# Sh1_MPU.net
KiCad netlist of a schematic drawn in Altium Designer
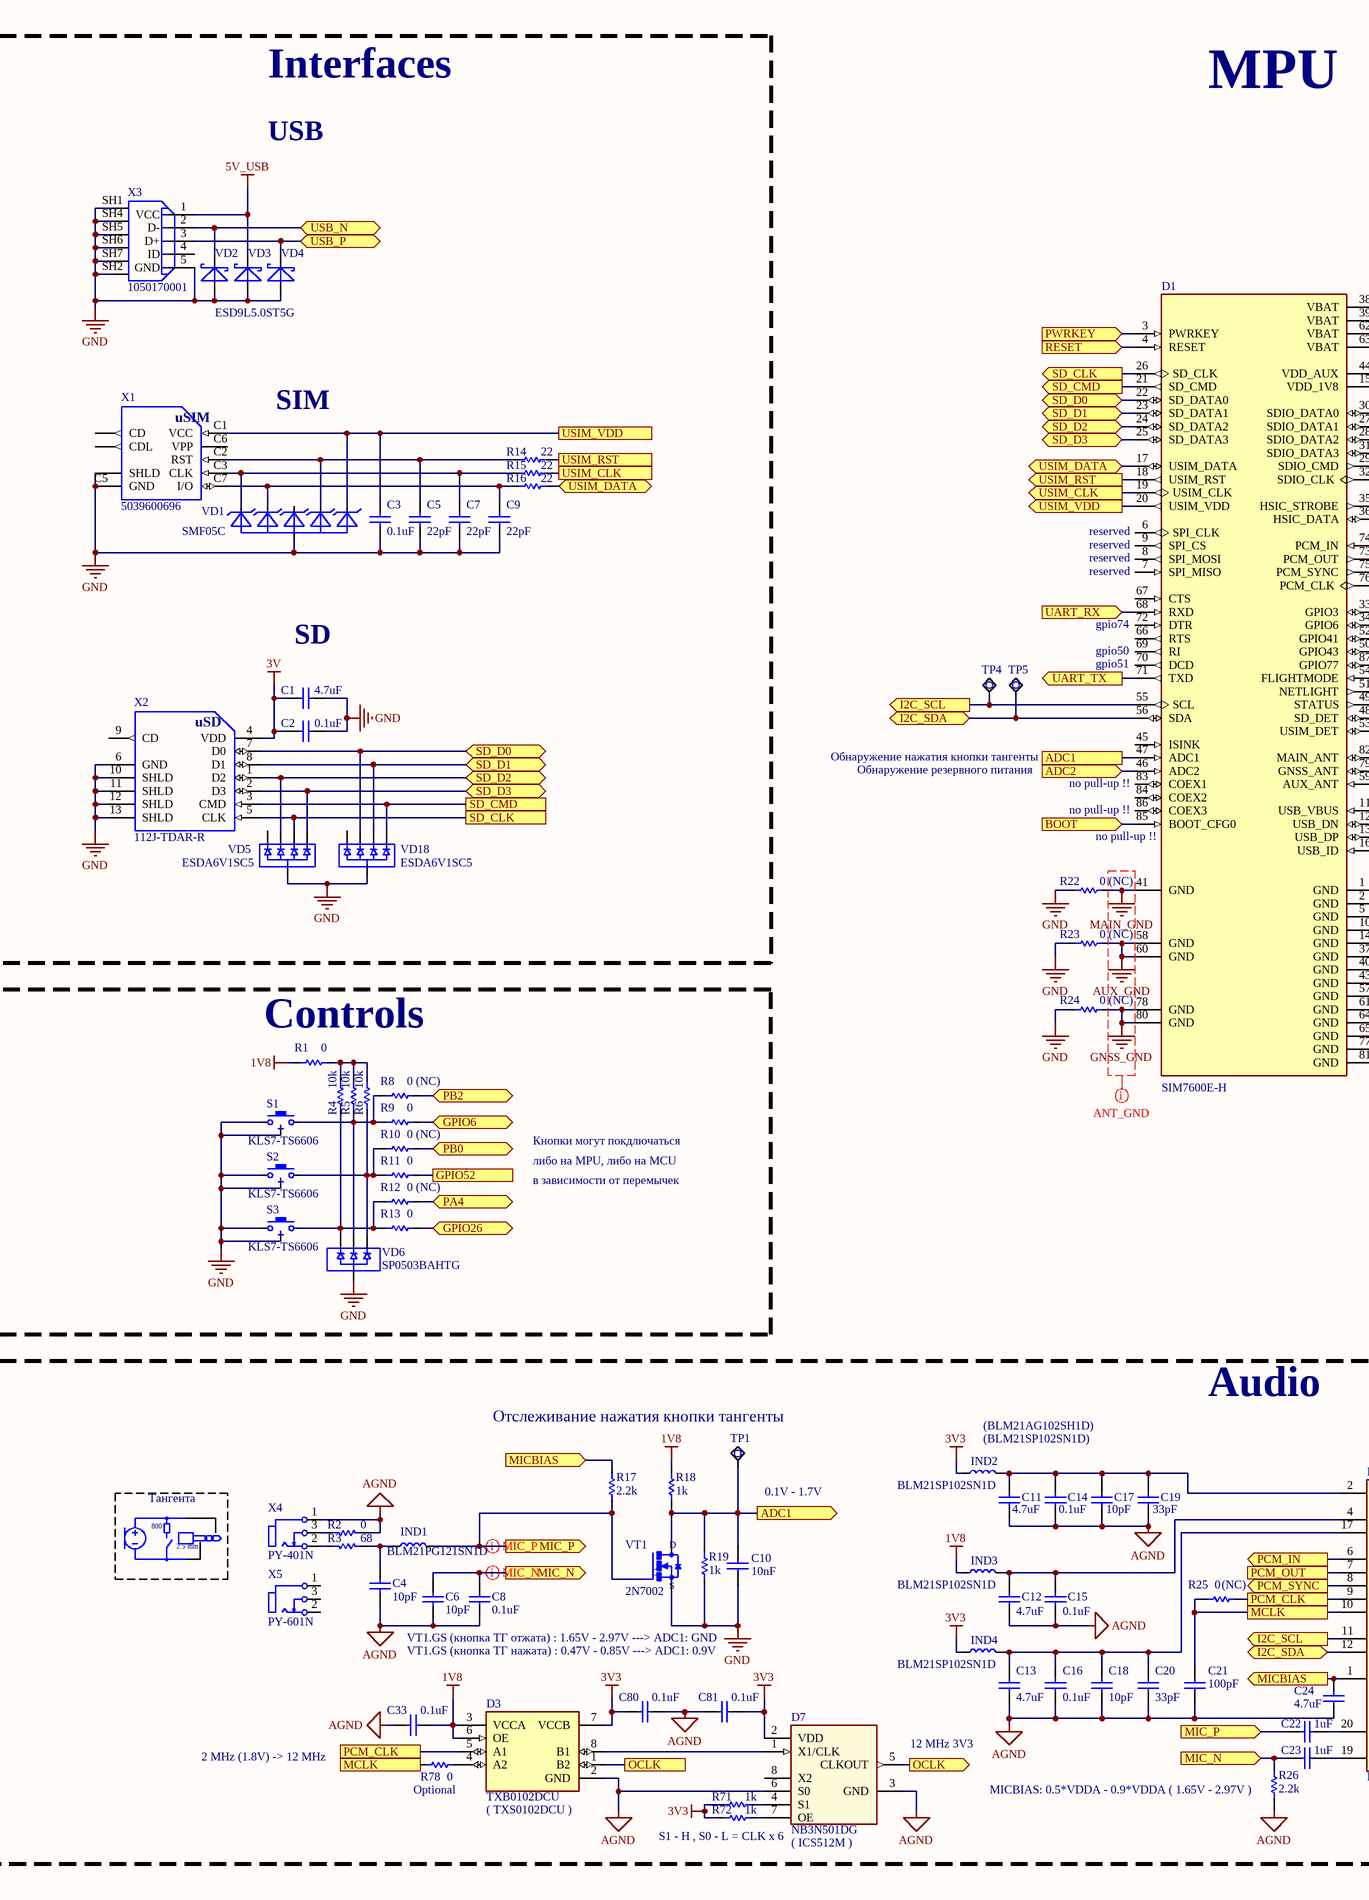
[diagram p0: Sh1_MPU.SchDoc, left]
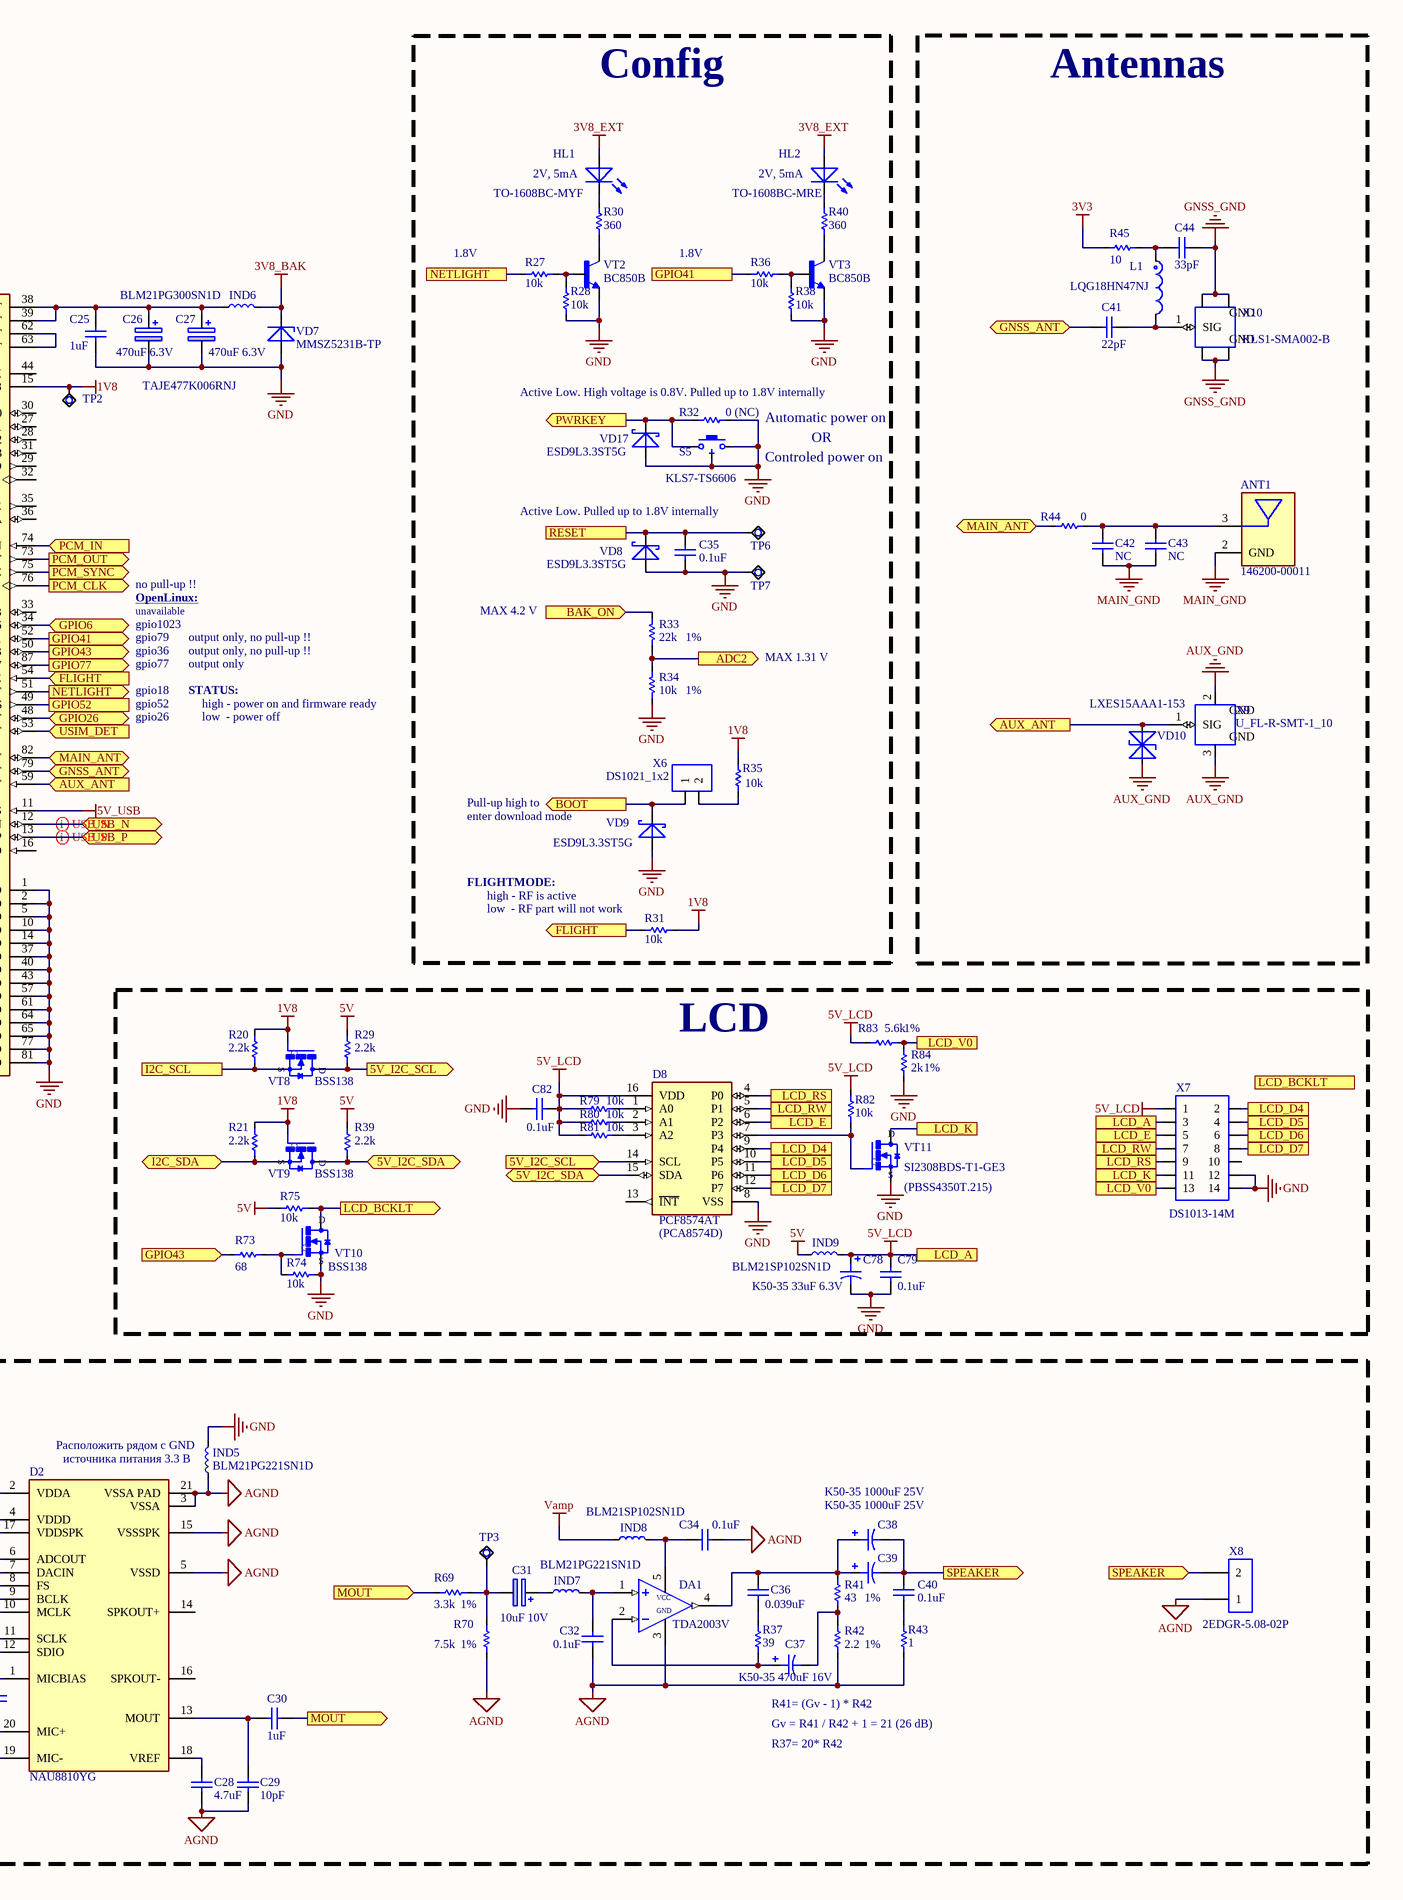
[diagram p1: Sh1_MPU.SchDoc, right]

(export (version "E")
  (design (tool "Eeschema 10.0.6"))
  (components
    (comp (ref "ANT1")
      (value "146200-00011")
      (footprint "Molex_146200-0011_MFG")
      (description "LTE Cellular Ceramic Antenna 698MHz-2.7GHz , SMT")
      (libsource (lib "MyCompLib") (part "146200-0001(11)"))
    )
    (comp (ref "C1")
      (value "4.7uF")
      (footprint "C_SMD0603")
      (description "GRM188R60J475KE19D")
      (libsource (lib "") (part "C_SMD_1"))
    )
    (comp (ref "C2")
      (value "0.1uF")
      (footprint "C_SMD0603")
      (description "GRM188R71H104KA93D")
      (libsource (lib "") (part "C_SMD_1"))
    )
    (comp (ref "C3")
      (value "0.1uF")
      (footprint "C_SMD0603")
      (description "GRM188R71H104KA93D")
      (libsource (lib "") (part "C_SMD_1"))
    )
    (comp (ref "C4")
      (value "10pF")
      (footprint "C_SMD0603")
      (description "GRM1885C1H100J")
      (libsource (lib "MyCompLib") (part "C_SMD"))
    )
    (comp (ref "C5")
      (value "22pF")
      (footprint "C_SMD0603")
      (description "GRM1885C1H220JA01D")
      (libsource (lib "") (part "C_SMD_1"))
    )
    (comp (ref "C6")
      (value "10pF")
      (footprint "C_SMD0603")
      (description "GRM1885C1H100J")
      (libsource (lib "MyCompLib") (part "C_SMD"))
    )
    (comp (ref "C7")
      (value "22pF")
      (footprint "C_SMD0603")
      (description "GRM1885C1H220JA01D")
      (libsource (lib "") (part "C_SMD_1"))
    )
    (comp (ref "C8")
      (value "0.1uF")
      (footprint "C_SMD0603")
      (description "GRM188R71H104KA93D")
      (libsource (lib "MyCompLib") (part "C_SMD"))
    )
    (comp (ref "C9")
      (value "22pF")
      (footprint "C_SMD0603")
      (description "GRM1885C1H220JA01D")
      (libsource (lib "") (part "C_SMD_1"))
    )
    (comp (ref "C10")
      (value "10nF")
      (footprint "C_SMD0603")
      (description "GRM188R71H103K")
      (libsource (lib "MyCompLib") (part "C_SMD"))
    )
    (comp (ref "C11")
      (value "4.7uF")
      (footprint "C_SMD0603")
      (description "GRM188R60J475KE19D")
      (libsource (lib "MyCompLib") (part "C_SMD"))
    )
    (comp (ref "C12")
      (value "4.7uF")
      (footprint "C_SMD0603")
      (description "GRM188R60J475KE19D")
      (libsource (lib "MyCompLib") (part "C_SMD"))
    )
    (comp (ref "C13")
      (value "4.7uF")
      (footprint "C_SMD0603")
      (description "GRM188R60J475KE19D")
      (libsource (lib "MyCompLib") (part "C_SMD"))
    )
    (comp (ref "C14")
      (value "0.1uF")
      (footprint "C_SMD0603")
      (description "GRM188R71H104KA93D")
      (libsource (lib "MyCompLib") (part "C_SMD"))
    )
    (comp (ref "C15")
      (value "0.1uF")
      (footprint "C_SMD0603")
      (description "GRM188R71H104KA93D")
      (libsource (lib "MyCompLib") (part "C_SMD"))
    )
    (comp (ref "C16")
      (value "0.1uF")
      (footprint "C_SMD0603")
      (description "GRM188R71H104KA93D")
      (libsource (lib "MyCompLib") (part "C_SMD"))
    )
    (comp (ref "C17")
      (value "10pF")
      (footprint "C_SMD0603")
      (description "GRM1885C1H100J")
      (libsource (lib "MyCompLib") (part "C_SMD"))
    )
    (comp (ref "C18")
      (value "10pF")
      (footprint "C_SMD0603")
      (description "GRM1885C1H100J")
      (libsource (lib "MyCompLib") (part "C_SMD"))
    )
    (comp (ref "C19")
      (value "33pF")
      (footprint "C_SMD0603")
      (description "GRM1885C1H330J")
      (libsource (lib "MyCompLib") (part "C_SMD"))
    )
    (comp (ref "C20")
      (value "33pF")
      (footprint "C_SMD0603")
      (description "GRM1885C1H330J")
      (libsource (lib "MyCompLib") (part "C_SMD"))
    )
    (comp (ref "C21")
      (value "100pF")
      (footprint "C_SMD0603")
      (description "GRM1885C1H101J")
      (libsource (lib "MyCompLib") (part "C_SMD"))
    )
    (comp (ref "C22")
      (value "1uF")
      (footprint "C_SMD0603")
      (description "GRM188R71E105KA12D")
      (libsource (lib "MyCompLib") (part "C_SMD"))
    )
    (comp (ref "C23")
      (value "1uF")
      (footprint "C_SMD0603")
      (description "GRM188R71E105KA12D")
      (libsource (lib "MyCompLib") (part "C_SMD"))
    )
    (comp (ref "C24")
      (value "4.7uF")
      (footprint "C_SMD0603")
      (description "GRM188R60J475KE19D")
      (libsource (lib "MyCompLib") (part "C_SMD"))
    )
    (comp (ref "C25")
      (value "1uF")
      (footprint "C_SMD0603")
      (description "GRM188R71E105KA12D")
      (libsource (lib "MyCompLib") (part "C_SMD"))
    )
    (comp (ref "C26")
      (value "470uF 6.3V")
      (footprint "TECAP_E")
      (description "293D477X06R3E2TE3\r\nКонденсатор танталовый SMD тип Е")
      (libsource (lib "MyCompLib") (part "C_SMD_Tantalum"))
    )
    (comp (ref "C27")
      (value "470uF 6.3V")
      (footprint "TECAP_E")
      (description "293D477X06R3E2TE3\r\nКонденсатор танталовый SMD тип Е")
      (libsource (lib "MyCompLib") (part "C_SMD_Tantalum"))
    )
    (comp (ref "C28")
      (value "4.7uF")
      (footprint "C_SMD0603")
      (description "GRM188R60J475KE19D")
      (libsource (lib "MyCompLib") (part "C_SMD"))
    )
    (comp (ref "C29")
      (value "10pF")
      (footprint "C_SMD0603")
      (description "GRM1885C1H100J")
      (libsource (lib "MyCompLib") (part "C_SMD"))
    )
    (comp (ref "C30")
      (value "1uF")
      (footprint "C_SMD1206")
      (description "GRM31MR71E105KA01L")
      (libsource (lib "MyCompLib") (part "C_SMD"))
    )
    (comp (ref "C31")
      (value "10uF 10V")
      (footprint "TECAP_B")
      (description "TAJB106K016RNJ\r\nКонденсатор танталовый SMD 10uF 10V тип B")
      (libsource (lib "") (part "C_SMD_Tantalum_1"))
    )
    (comp (ref "C32")
      (value "0.1uF")
      (footprint "C_SMD0603")
      (description "GRM188R71H104KA93D")
      (libsource (lib "MyCompLib") (part "C_SMD"))
    )
    (comp (ref "C33")
      (value "0.1uF")
      (footprint "C_SMD0402")
      (description "CL05B104KO5NNNC")
      (libsource (lib "MyCompLib") (part "C_SMD"))
    )
    (comp (ref "C34")
      (value "0.1uF")
      (footprint "C_SMD0603")
      (description "GRM188R71H104KA93D")
      (libsource (lib "MyCompLib") (part "C_SMD"))
    )
    (comp (ref "C35")
      (value "0.1uF")
      (footprint "C_SMD0603")
      (description "GRM188R71H104KA93D")
      (libsource (lib "MyCompLib") (part "C_SMD"))
    )
    (comp (ref "C36")
      (value "0.039uF")
      (footprint "C_SMD0603")
      (description "CC0603KRX7R9BB393")
      (libsource (lib "MyCompLib") (part "C_SMD"))
    )
    (comp (ref "C37")
      (value "K50-35 470uF 16V")
      (footprint "K50-35 8x11.5x3.5")
      (description "Конденсатор электролитический алюминиевый 470мкФ, 16В 8х12мм Р:3.5мм")
      (libsource (lib "MyCompLib") (part "K50-35"))
    )
    (comp (ref "C38")
      (value "K50-35 1000uF 25V")
      (footprint "K50-35 10x12.5x5")
      (description "Конденсатор электролитический алюминиевый 1000мкФ, 16В, 10x21мм")
      (libsource (lib "MyCompLib") (part "K50-35"))
    )
    (comp (ref "C39")
      (value "K50-35 1000uF 25V")
      (footprint "K50-35 10x12.5x5")
      (description "Конденсатор электролитический алюминиевый 1000мкФ, 16В, 10x21мм")
      (libsource (lib "MyCompLib") (part "K50-35"))
    )
    (comp (ref "C40")
      (value "0.1uF")
      (footprint "C_SMD0603")
      (description "GRM188R71H104KA93D")
      (libsource (lib "MyCompLib") (part "C_SMD"))
    )
    (comp (ref "C41")
      (value "22pF")
      (footprint "C_SMD0805")
      (description "GRM21A5C2E220J")
      (libsource (lib "MyCompLib") (part "C_SMD"))
    )
    (comp (ref "C42")
      (value "NС")
      (footprint "C_SMD0603")
      (description "0603 SMD Capacitor")
      (libsource (lib "MyCompLib") (part "C_SMD"))
    )
    (comp (ref "C43")
      (value "NС")
      (footprint "C_SMD0603")
      (description "0603 SMD Capacitor")
      (libsource (lib "MyCompLib") (part "C_SMD"))
    )
    (comp (ref "C44")
      (value "33pF")
      (footprint "C_SMD0603")
      (description "GRM1885C1H330J")
      (libsource (lib "MyCompLib") (part "C_SMD"))
    )
    (comp (ref "C78")
      (value "K50-35 33uF 6.3V")
      (footprint "K50-35mini 4x7x2")
      (description "Конденсатор электролитический алюминиевый 33 мкФ, 6.3 В, 4х7мм")
      (libsource (lib "MyCompLib") (part "K50-35"))
    )
    (comp (ref "C79")
      (value "0.1uF")
      (footprint "C_SMD0603")
      (description "GRM188R71H104KA93D")
      (libsource (lib "MyCompLib") (part "C_SMD"))
    )
    (comp (ref "C80")
      (value "0.1uF")
      (footprint "C_SMD0402")
      (description "CL05B104KO5NNNC")
      (libsource (lib "MyCompLib") (part "C_SMD"))
    )
    (comp (ref "C81")
      (value "0.1uF")
      (footprint "C_SMD0402")
      (description "CL05B104KO5NNNC")
      (libsource (lib "MyCompLib") (part "C_SMD"))
    )
    (comp (ref "C82")
      (value "0.1uF")
      (footprint "C_SMD0603")
      (description "GRM188R71H104KA93D")
      (libsource (lib "MyCompLib") (part "C_SMD"))
    )
    (comp (ref "D1")
      (value "SIM7600E-H")
      (footprint "IC_SIM7600E-H")
      (description "Multi-Band LTE-TDD/LTE-FDD/HSPA+ and GSM/GPRS/EDGE module")
      (fields (field (name "MF") "Simcom"))
      (libsource (lib "MyCompLib") (part "SIM7600E-H"))
    )
    (comp (ref "D2")
      (value "NAU8810YG")
      (footprint "NAU8810YG")
      (description "AUDIO CODEC MONO 20QFN")
      (fields (field (name "VOLTAGE") "3.6V") (field (name "MANUFACTURER") "Nuvoton Technology Corporation"))
      (libsource (lib "MyCompLib") (part "NAU8810YG"))
    )
    (comp (ref "D3")
      (value "TXB0102DCU")
      (footprint "SOP50P310X90-8N")
      (description "Voltage Level Translator Bidirectional 1 Circuit 2 Channel 100Mbps 8-VSSOP")
      (fields (field (name "MF") "Texas Instruments") (field (name "MP") "TXB0102"))
      (libsource (lib "MyCompLib") (part "TXB0102"))
    )
    (comp (ref "D7")
      (value "NB3N501DG")
      (footprint "SOIC8 (SO-8)")
      (description "PLL Clock Multiplier Single 8-Pin SOIC 3 V ~ 5.25 V")
      (libsource (lib "MyCompLib") (part "NB3N501DG"))
    )
    (comp (ref "D8")
      (value "PCF8574AT")
      (footprint "SOIC127P1032X265-16N")
      (fields (field (name "MF") "NXP Semiconductors"))
      (libsource (lib "MyCompLib") (part "PCF8574AT"))
    )
    (comp (ref "DA1")
      (value "TDA2003V")
      (footprint "TDA2003V _HS-117-30 (ABM-161-30)")
      (description "Amplifier IC 1-Channel _Mono_ Class AB 5-PENTAWATT 10W")
      (fields (field (name "MF") "STMicroelectronics"))
      (libsource (lib "MyCompLib") (part "TDA2003V"))
    )
    (comp (ref "HL1")
      (value "TO-1608BC-MYF")
      (footprint "LED_SMD1608 + THR0254")
      (description "Vf =2 V, 20mA, 0603 (HL-PST-1608S31YC)")
      (libsource (lib "MyCompLib") (part "LED_SMD"))
    )
    (comp (ref "HL2")
      (value "TO-1608BC-MRE")
      (footprint "LED_SMD1608 + THR0254")
      (description "Vf =2 V, 20mA, 0603 (HL-PST-1608S9AC)")
      (libsource (lib "MyCompLib") (part "LED_SMD"))
    )
    (comp (ref "IND1")
      (value "BLM21PG121SN1D")
      (footprint "BLM21PG221_0805")
      (description "0805, Дроссель подавления ЭМП 120Ohm 25% 100MHz 3A")
      (libsource (lib "") (part "BLM21PG221SN1D_1"))
    )
    (comp (ref "IND2")
      (value "BLM21SP102SN1D")
      (footprint "BLM21PG221_0805")
      (description "0805, Дроссель подавления ЭМП 1KOhm 25% 100MHz 1.6A 0.12Ohm")
      (libsource (lib "MyCompLib") (part "BLM21PG221SN1D"))
    )
    (comp (ref "IND3")
      (value "BLM21SP102SN1D")
      (footprint "BLM21PG221_0805")
      (description "0805, Дроссель подавления ЭМП 1KOhm 25% 100MHz 1.6A 0.12Ohm")
      (libsource (lib "MyCompLib") (part "BLM21PG221SN1D"))
    )
    (comp (ref "IND4")
      (value "BLM21SP102SN1D")
      (footprint "BLM21PG221_0805")
      (description "0805, Дроссель подавления ЭМП 1KOhm 25% 100MHz 1.6A 0.12Ohm")
      (libsource (lib "MyCompLib") (part "BLM21PG221SN1D"))
    )
    (comp (ref "IND5")
      (value "BLM21PG221SN1D")
      (footprint "BLM21PG221_0805")
      (description "0805, Дроссель подавления ЭМП 220Ohm +25% 100MHz 2A 45mOhm")
      (libsource (lib "MyCompLib") (part "BLM21PG221SN1D"))
    )
    (comp (ref "IND6")
      (value "BLM21PG300SN1D")
      (footprint "BLM21PG221_0805")
      (description "0805, Дроссель подавления ЭМП 100МГц:30Ом; 3А")
      (libsource (lib "MyCompLib") (part "BLM21PG221SN1D"))
    )
    (comp (ref "IND7")
      (value "BLM21PG221SN1D")
      (footprint "BLM21PG221_0805")
      (description "0805, Дроссель подавления ЭМП 220Ohm +25% 100MHz 2A 45mOhm")
      (libsource (lib "MyCompLib") (part "BLM21PG221SN1D"))
    )
    (comp (ref "IND8")
      (value "BLM21SP102SN1D")
      (footprint "BLM21PG221_0805")
      (description "0805, Дроссель подавления ЭМП 1KOhm 25% 100MHz 1.6A 0.12Ohm")
      (libsource (lib "MyCompLib") (part "BLM21PG221SN1D"))
    )
    (comp (ref "IND9")
      (value "BLM21SP102SN1D")
      (footprint "BLM21PG221_0805")
      (description "0805, Дроссель подавления ЭМП 1KOhm 25% 100MHz 1.6A 0.12Ohm")
      (libsource (lib "MyCompLib") (part "BLM21PG221SN1D"))
    )
    (comp (ref "L1")
      (value "LQG18HN47NJ")
      (footprint "L0603")
      (libsource (lib "MyCompLib") (part "LQG18HN47NJ"))
    )
    (comp (ref "R1")
      (value "0")
      (footprint "R_SMD0603")
      (description "RC0603JR-070RL")
      (libsource (lib "MyCompLib") (part "R_SMD"))
    )
    (comp (ref "R2")
      (value "0")
      (footprint "R_SMD0603")
      (description "RC0603JR-070RL")
      (libsource (lib "MyCompLib") (part "R_SMD"))
    )
    (comp (ref "R3")
      (value "68")
      (footprint "R_SMD0603")
      (description "RC0603FR-0768RL")
      (libsource (lib "MyCompLib") (part "R_SMD"))
    )
    (comp (ref "R4")
      (value "10k")
      (footprint "R_SMD0603")
      (description "RC0603FR-0710KL (CRCW060310K0FKEA)")
      (libsource (lib "MyCompLib") (part "R_SMD"))
    )
    (comp (ref "R5")
      (value "10k")
      (footprint "R_SMD0603")
      (description "RC0603FR-0710KL (CRCW060310K0FKEA)")
      (libsource (lib "MyCompLib") (part "R_SMD"))
    )
    (comp (ref "R6")
      (value "10k")
      (footprint "R_SMD0603")
      (description "RC0603FR-0710KL (CRCW060310K0FKEA)")
      (libsource (lib "MyCompLib") (part "R_SMD"))
    )
    (comp (ref "R8")
      (value "0 (NC)")
      (footprint "R_SMD0603")
      (description "RC0603JR-070RL")
      (libsource (lib "MyCompLib") (part "R_SMD"))
    )
    (comp (ref "R9")
      (value "0")
      (footprint "R_SMD0603")
      (description "RC0603JR-070RL")
      (libsource (lib "MyCompLib") (part "R_SMD"))
    )
    (comp (ref "R10")
      (value "0 (NC)")
      (footprint "R_SMD0603")
      (description "RC0603JR-070RL")
      (libsource (lib "MyCompLib") (part "R_SMD"))
    )
    (comp (ref "R11")
      (value "0")
      (footprint "R_SMD0603")
      (description "RC0603JR-070RL")
      (libsource (lib "MyCompLib") (part "R_SMD"))
    )
    (comp (ref "R12")
      (value "0 (NC)")
      (footprint "R_SMD0603")
      (description "RC0603JR-070RL")
      (libsource (lib "MyCompLib") (part "R_SMD"))
    )
    (comp (ref "R13")
      (value "0")
      (footprint "R_SMD0603")
      (description "RC0603JR-070RL")
      (libsource (lib "MyCompLib") (part "R_SMD"))
    )
    (comp (ref "R14")
      (value "22")
      (footprint "R_SMD0603")
      (description "RC0603FR-0722RL (RC0603JR-0722RL)")
      (libsource (lib "MyCompLib") (part "R_SMD"))
    )
    (comp (ref "R15")
      (value "22")
      (footprint "R_SMD0603")
      (description "RC0603FR-0722RL (RC0603JR-0722RL)")
      (libsource (lib "MyCompLib") (part "R_SMD"))
    )
    (comp (ref "R16")
      (value "22")
      (footprint "R_SMD0603")
      (description "RC0603FR-0722RL (RC0603JR-0722RL)")
      (libsource (lib "MyCompLib") (part "R_SMD"))
    )
    (comp (ref "R17")
      (value "2.2k")
      (footprint "R_SMD0603")
      (description "RC0603FR-072K2L")
      (libsource (lib "MyCompLib") (part "R_SMD"))
    )
    (comp (ref "R18")
      (value "1k")
      (footprint "R_SMD0603")
      (description "RC0603FR-071KL")
      (libsource (lib "MyCompLib") (part "R_SMD"))
    )
    (comp (ref "R19")
      (value "1k")
      (footprint "R_SMD0603")
      (description "RC0603FR-071KL")
      (libsource (lib "MyCompLib") (part "R_SMD"))
    )
    (comp (ref "R20")
      (value "2.2k")
      (footprint "R_SMD0603")
      (description "RC0603FR-072K2L")
      (libsource (lib "MyCompLib") (part "R_SMD"))
    )
    (comp (ref "R21")
      (value "2.2k")
      (footprint "R_SMD0603")
      (description "RC0603FR-072K2L")
      (libsource (lib "MyCompLib") (part "R_SMD"))
    )
    (comp (ref "R22")
      (value "0 (NC)")
      (footprint "R_SMD0805")
      (description "RC0805JR-070RL")
      (libsource (lib "MyCompLib") (part "R_SMD"))
    )
    (comp (ref "R23")
      (value "0 (NC)")
      (footprint "R_SMD0805")
      (description "RC0805JR-070RL")
      (libsource (lib "MyCompLib") (part "R_SMD"))
    )
    (comp (ref "R24")
      (value "0 (NC)")
      (footprint "R_SMD0805")
      (description "RC0805JR-070RL")
      (libsource (lib "MyCompLib") (part "R_SMD"))
    )
    (comp (ref "R25")
      (value "0")
      (footprint "R_SMD0603")
      (description "RC0603JR-070RL")
      (libsource (lib "MyCompLib") (part "R_SMD"))
    )
    (comp (ref "R26")
      (value "2.2k")
      (footprint "R_SMD0603")
      (description "RC0603FR-072K2L")
      (libsource (lib "MyCompLib") (part "R_SMD"))
    )
    (comp (ref "R27")
      (value "10k")
      (footprint "R_SMD0603")
      (description "RC0603FR-0710KL (CRCW060310K0FKEA)")
      (libsource (lib "MyCompLib") (part "R_SMD"))
    )
    (comp (ref "R28")
      (value "10k")
      (footprint "R_SMD0603")
      (description "RC0603FR-0710KL (CRCW060310K0FKEA)")
      (libsource (lib "MyCompLib") (part "R_SMD"))
    )
    (comp (ref "R29")
      (value "2.2k")
      (footprint "R_SMD0603")
      (description "RC0603FR-072K2L")
      (libsource (lib "MyCompLib") (part "R_SMD"))
    )
    (comp (ref "R30")
      (value "360")
      (footprint "R_SMD0603")
      (description "RC0603FR-07360RL")
      (libsource (lib "MyCompLib") (part "R_SMD"))
    )
    (comp (ref "R31")
      (value "10k")
      (footprint "R_SMD0603")
      (description "RC0603FR-0710KL (CRCW060310K0FKEA)")
      (libsource (lib "MyCompLib") (part "R_SMD"))
    )
    (comp (ref "R32")
      (value "0 (NC)")
      (footprint "R_SMD0603")
      (description "RC0603JR-070RL")
      (libsource (lib "MyCompLib") (part "R_SMD"))
    )
    (comp (ref "R33")
      (value "22k")
      (footprint "R_SMD0603")
      (description "RC0603FR-0722KL")
      (libsource (lib "MyCompLib") (part "R_SMD"))
    )
    (comp (ref "R34")
      (value "10k")
      (footprint "R_SMD0603")
      (description "RC0603FR-0710KL (CRCW060310K0FKEA)")
      (libsource (lib "MyCompLib") (part "R_SMD"))
    )
    (comp (ref "R35")
      (value "10k")
      (footprint "R_SMD0603")
      (description "RC0603FR-0710KL (CRCW060310K0FKEA)")
      (libsource (lib "MyCompLib") (part "R_SMD"))
    )
    (comp (ref "R36")
      (value "10k")
      (footprint "R_SMD0603")
      (description "RC0603FR-0710KL (CRCW060310K0FKEA)")
      (libsource (lib "MyCompLib") (part "R_SMD"))
    )
    (comp (ref "R37")
      (value "39")
      (footprint "R_SMD0603")
      (description "RC0603FR-0739RL")
      (libsource (lib "MyCompLib") (part "R_SMD"))
    )
    (comp (ref "R38")
      (value "10k")
      (footprint "R_SMD0603")
      (description "RC0603FR-0710KL (CRCW060310K0FKEA)")
      (libsource (lib "MyCompLib") (part "R_SMD"))
    )
    (comp (ref "R39")
      (value "2.2k")
      (footprint "R_SMD0603")
      (description "RC0603FR-072K2L")
      (libsource (lib "MyCompLib") (part "R_SMD"))
    )
    (comp (ref "R40")
      (value "360")
      (footprint "R_SMD0603")
      (description "RC0603FR-07360RL")
      (libsource (lib "MyCompLib") (part "R_SMD"))
    )
    (comp (ref "R41")
      (value "43")
      (footprint "R_SMD0603")
      (description "RC0603FR-0743RL")
      (libsource (lib "MyCompLib") (part "R_SMD"))
    )
    (comp (ref "R42")
      (value "2.2")
      (footprint "R_SMD0603")
      (description "RC0603FR-072R2L")
      (libsource (lib "MyCompLib") (part "R_SMD"))
    )
    (comp (ref "R43")
      (value "1")
      (footprint "R_SMD0603")
      (description "RC0603FR-071RL")
      (libsource (lib "MyCompLib") (part "R_SMD"))
    )
    (comp (ref "R44")
      (value "0")
      (footprint "R_SMD0805")
      (description "RC0805JR-070RL")
      (libsource (lib "MyCompLib") (part "R_SMD"))
    )
    (comp (ref "R45")
      (value "10")
      (footprint "R_SMD0603")
      (description "RC0603FR-0710RL")
      (libsource (lib "MyCompLib") (part "R_SMD"))
    )
    (comp (ref "R69")
      (value "3.3k")
      (footprint "R_SMD0603")
      (description "RC0603FR-073K3L")
      (libsource (lib "MyCompLib") (part "R_SMD"))
    )
    (comp (ref "R70")
      (value "7.5k")
      (footprint "R_SMD0603")
      (description "RC0603FR-077K5L")
      (libsource (lib "MyCompLib") (part "R_SMD"))
    )
    (comp (ref "R71")
      (value "1k")
      (footprint "R_SMD0402")
      (description "RC0402FR-071KL")
      (libsource (lib "MyCompLib") (part "R_SMD"))
    )
    (comp (ref "R72")
      (value "1k")
      (footprint "R_SMD1206")
      (description "RC1206FR-071KL")
      (libsource (lib "MyCompLib") (part "R_SMD"))
    )
    (comp (ref "R73")
      (value "68")
      (footprint "R_SMD0603")
      (description "RC0603FR-0768RL")
      (libsource (lib "MyCompLib") (part "R_SMD"))
    )
    (comp (ref "R74")
      (value "10k")
      (footprint "R_SMD0603")
      (description "RC0603FR-0710KL (CRCW060310K0FKEA)")
      (libsource (lib "MyCompLib") (part "R_SMD"))
    )
    (comp (ref "R75")
      (value "10k")
      (footprint "R_SMD0603")
      (description "RC0603FR-0710KL (CRCW060310K0FKEA)")
      (libsource (lib "MyCompLib") (part "R_SMD"))
    )
    (comp (ref "R78")
      (value "0")
      (footprint "R_SMD0603")
      (description "RC0603JR-070RL")
      (libsource (lib "MyCompLib") (part "R_SMD"))
    )
    (comp (ref "R79")
      (value "10k")
      (footprint "R_SMD0603")
      (description "RC0603FR-0710KL (CRCW060310K0FKEA)")
      (libsource (lib "MyCompLib") (part "R_SMD"))
    )
    (comp (ref "R80")
      (value "10k")
      (footprint "R_SMD0603")
      (description "RC0603FR-0710KL (CRCW060310K0FKEA)")
      (libsource (lib "MyCompLib") (part "R_SMD"))
    )
    (comp (ref "R81")
      (value "10k")
      (footprint "R_SMD0603")
      (description "RC0603FR-0710KL (CRCW060310K0FKEA)")
      (libsource (lib "MyCompLib") (part "R_SMD"))
    )
    (comp (ref "R82")
      (value "10k")
      (footprint "R_SMD0603")
      (description "RC0603FR-0710KL (CRCW060310K0FKEA)")
      (libsource (lib "MyCompLib") (part "R_SMD"))
    )
    (comp (ref "R83")
      (value "5.6k")
      (footprint "R_SMD0603")
      (description "RC0603FR-075K6L")
      (libsource (lib "MyCompLib") (part "R_SMD"))
    )
    (comp (ref "R84")
      (value "2k")
      (footprint "R_SMD0603")
      (description "RC0603FR-072KL")
      (libsource (lib "MyCompLib") (part "R_SMD"))
    )
    (comp (ref "S1")
      (value "KLS7-TS6606")
      (footprint "KLS7-TS6606 -7.0")
      (description "6x6 Tact Switch Series")
      (libsource (lib "MyCompLib") (part "KLS7-TS6606-8-180"))
    )
    (comp (ref "S2")
      (value "KLS7-TS6606")
      (footprint "KLS7-TS6606 -7.0")
      (description "6x6 Tact Switch Series")
      (libsource (lib "MyCompLib") (part "KLS7-TS6606-8-180"))
    )
    (comp (ref "S3")
      (value "KLS7-TS6606")
      (footprint "KLS7-TS6606 -7.0")
      (description "6x6 Tact Switch Series")
      (libsource (lib "MyCompLib") (part "KLS7-TS6606-8-180"))
    )
    (comp (ref "S5")
      (value "KLS7-TS6606")
      (footprint "KLS7-TS6606 -7.0")
      (description "6x6 Tact Switch Series")
      (libsource (lib "") (part "KLS7-TS6606-8-180_1"))
    )
    (comp (ref "TP1")
      (value "Test_point")
      (footprint "TEST_POINT")
      (description "Test point for PCB")
      (libsource (lib "MyCompLib") (part "Test_point"))
    )
    (comp (ref "TP2")
      (value "Test_point")
      (footprint "TEST_POINT")
      (description "Test point for PCB")
      (libsource (lib "MyCompLib") (part "Test_point"))
    )
    (comp (ref "TP3")
      (value "Test_point")
      (footprint "TEST_POINT")
      (description "Test point for PCB")
      (libsource (lib "MyCompLib") (part "Test_point"))
    )
    (comp (ref "TP4")
      (value "Test_point")
      (footprint "TEST_POINT")
      (description "Test point for PCB")
      (libsource (lib "MyCompLib") (part "Test_point"))
    )
    (comp (ref "TP5")
      (value "Test_point")
      (footprint "TEST_POINT")
      (description "Test point for PCB")
      (libsource (lib "MyCompLib") (part "Test_point"))
    )
    (comp (ref "TP6")
      (value "Test_point")
      (footprint "TEST_POINT")
      (description "Test point for PCB")
      (libsource (lib "MyCompLib") (part "Test_point"))
    )
    (comp (ref "TP7")
      (value "Test_point")
      (footprint "TEST_POINT")
      (description "Test point for PCB")
      (libsource (lib "MyCompLib") (part "Test_point"))
    )
    (comp (ref "VD1")
      (value "SMF05C")
      (footprint "SMF05C")
      (description "12.5V Clamp 8A _8/20µs_ Ipp Tvs Diode Surface Mount SC-88/SC70-6/SOT-363")
      (fields (field (name "MF") "ON Semiconductor"))
      (libsource (lib "MyCompLib") (part "SMF05C"))
    )
    (comp (ref "VD2")
      (value "ESD9L5.0ST5G")
      (footprint "ESD9L5_514AB")
      (description "TVS диод защитный 5В_пиковое_рабочее 9.8В_ограничение SOD923")
      (libsource (lib "MyCompLib") (part "ESD9L5.0ST5G"))
    )
    (comp (ref "VD3")
      (value "ESD9L5.0ST5G")
      (footprint "ESD9L5_514AB")
      (description "TVS диод защитный 5В_пиковое_рабочее 9.8В_ограничение SOD923")
      (libsource (lib "MyCompLib") (part "ESD9L5.0ST5G"))
    )
    (comp (ref "VD4")
      (value "ESD9L5.0ST5G")
      (footprint "ESD9L5_514AB")
      (description "TVS диод защитный 5В_пиковое_рабочее 9.8В_ограничение SOD923")
      (libsource (lib "MyCompLib") (part "ESD9L5.0ST5G"))
    )
    (comp (ref "VD5")
      (value "ESDA6V1SC5")
      (footprint "SOT23-5")
      (fields (field (name "MF") "STMicroelectronics") (field (name "MP") "ESDA6V1W5"))
      (libsource (lib "MyCompLib") (part "ESDA6V1SC5"))
    )
    (comp (ref "VD6")
      (value "SP0503BAHTG")
      (footprint "SP0503BAHTG")
      (description "TVS Diode-3 Рабочее напряжение 5.5 В\r\nМаксимальное напряжение фиксации 8.5 в")
      (libsource (lib "MyCompLib") (part "SP0503BAHTG"))
    )
    (comp (ref "VD7")
      (value "MMSZ5231B-TP")
      (footprint "SOD-123_3716X135N")
      (description "Стабилитрон 5.1В, 5%, 0.5Вт, [SOD-123]")
      (libsource (lib "MyCompLib") (part "MMSZ5231B-TP"))
    )
    (comp (ref "VD8")
      (value "ESD9L3.3ST5G")
      (footprint "ESD9L5_514AB")
      (description "TVS диод защитный 5В_пиковое_рабочее 9.8В_ограничение SOD923")
      (libsource (lib "MyCompLib") (part "ESD9L5.0ST5G"))
    )
    (comp (ref "VD9")
      (value "ESD9L3.3ST5G")
      (footprint "ESD9L5_514AB")
      (description "TVS диод защитный 5В_пиковое_рабочее 9.8В_ограничение SOD923")
      (libsource (lib "MyCompLib") (part "ESD9L5.0ST5G"))
    )
    (comp (ref "VD10")
      (value "LXES15AAA1-153")
      (footprint "Murata_LXES15_IPC_A")
      (libsource (lib "MyCompLib") (part "LXES15AAA1-153"))
    )
    (comp (ref "VD17")
      (value "ESD9L3.3ST5G")
      (footprint "ESD9L5_514AB")
      (description "TVS диод защитный 5В_пиковое_рабочее 9.8В_ограничение SOD923")
      (libsource (lib "MyCompLib") (part "ESD9L5.0ST5G"))
    )
    (comp (ref "VD18")
      (value "ESDA6V1SC5")
      (footprint "SOT23-5")
      (fields (field (name "MF") "STMicroelectronics") (field (name "MP") "ESDA6V1W5"))
      (libsource (lib "MyCompLib") (part "ESDA6V1SC5"))
    )
    (comp (ref "VT1")
      (value "2N7002")
      (footprint "SOT23")
      (description "N-Channel MOSFET 60В 0.115А [SOT-23]")
      (libsource (lib "MyCompLib") (part "2N7002"))
    )
    (comp (ref "VT2")
      (value "BC850B")
      (footprint "SOT23-3")
      (description "Transistor, Npn, 0.1A, 50V, Vbe = 0.7V, hfe = 240 [ SOT23 ]")
      (libsource (lib "MyCompLib") (part "BC850B"))
    )
    (comp (ref "VT3")
      (value "BC850B")
      (footprint "SOT23-3")
      (description "Transistor, Npn, 0.1A, 50V, Vbe = 0.7V, hfe = 240 [ SOT23 ]")
      (libsource (lib "MyCompLib") (part "BC850B"))
    )
    (comp (ref "VT8")
      (value "BSS138")
      (footprint "SOT23-3")
      (description "MOSFET, N-канал, 0.2А, 50В, [SOT-23]")
      (libsource (lib "MyCompLib") (part "BSS138"))
    )
    (comp (ref "VT9")
      (value "BSS138")
      (footprint "SOT23-3")
      (description "MOSFET, N-канал, 0.2А, 50В, [SOT-23]")
      (libsource (lib "MyCompLib") (part "BSS138"))
    )
    (comp (ref "VT10")
      (value "BSS138")
      (footprint "SOT23-3")
      (description "MOSFET, N-канал, 0.2А, 50В, [SOT-23]")
      (libsource (lib "") (part "BSS138_1"))
    )
    (comp (ref "VT11")
      (value "SI2308BDS-T1-GE3")
      (footprint "SOT23")
      (description "MOSFET, N-канал 60В 1.9А [SOT-23]")
      (libsource (lib "MyCompLib") (part "SI2308BDS-T1-GE3"))
    )
    (comp (ref "X1")
      (value "5039600696")
      (footprint "MOLEX_uSIM_5039600696")
      (description "Соединители для карт памяти 1mm microSIM Push Push SMT")
      (libsource (lib "MyCompLib") (part "microSIM_Holder_5039600696"))
    )
    (comp (ref "X2")
      (value "112J-TDAR-R")
      (footprint "112JTDARR")
      (description "Разъем: для карт памяти; SD Micro; push-push; SMT; позолота")
      (libsource (lib "MyCompLib") (part "microSD_112J-TDAR-R"))
    )
    (comp (ref "X3")
      (value "1050170001")
      (footprint "MOLEX_1050170001 - compact")
      (description "USB - micro B USB 2.0 Receptacle Connector 5 Position Surface Mount, Right Angle; Through Hole")
      (fields (field (name "MF") "Molex") (field (name "DIGI-KEY_PART_NUMBER") "WM1399CT-ND"))
      (libsource (lib "MyCompLib") (part "microUSB_1050170001"))
    )
    (comp (ref "X4")
      (value "PY-401N")
      (footprint "PY-401N - compact")
      (description "Гнездо моно 2.5мм")
      (libsource (lib "MyCompLib") (part "microJACK PY-401N"))
    )
    (comp (ref "X5")
      (value "PY-601N")
      (footprint "PY-601N - compact")
      (description "Аудио гнездо (М) 3.5мм")
      (libsource (lib "MyCompLib") (part "miniJACK PY-601N"))
    )
    (comp (ref "X6")
      (value "DS1021_1x2")
      (footprint "PLD2")
      (description "Вилка штыревая 2.54мм 1x2 прямая PLS-2")
      (libsource (lib "MyCompLib") (part "DS1021_1x2"))
    )
    (comp (ref "X7")
      (value "DS1013-14M")
      (footprint "IDC-14M")
      (libsource (lib "MyCompLib") (part "DS1013-14S"))
    )
    (comp (ref "X8")
      (value "2EDGR-5.08-02P")
      (footprint "2EDGR-5.08-02P")
      (libsource (lib "MyCompLib") (part "2EDGR-5.08-02P"))
    )
    (comp (ref "X9")
      (value "U_FL-R-SMT-1_10")
      (footprint "HIROSE_0_MFG")
      (libsource (lib "MyCompLib") (part "U_FL-R-SMT-1_10"))
    )
    (comp (ref "X10")
      (value "KLS1-SMA002-B")
      (footprint "SMA-FEMALE-RA - L-KLS1-SMA002-B")
      (description "Разъем угловой SMA гнездо на плату 50 Ом")
      (libsource (lib "MyCompLib") (part "SMA-connector"))
    )
  )
  (nets
    (net (code "1") (name "/5V_I2C_SCL") (class "Default")
      (node (ref "D8") (pin "14") (pinfunction "SCL_14") (pintype "input"))
      (node (ref "R29") (pin "2") (pinfunction "CW_2") (pintype "passive"))
      (node (ref "VT8") (pin "3") (pinfunction "D_3") (pintype "passive"))
    )
    (net (code "2") (name "/5V_I2C_SDA") (class "Default")
      (node (ref "D8") (pin "15") (pinfunction "SDA_15") (pintype "bidirectional"))
      (node (ref "R39") (pin "1") (pinfunction "CCW_1") (pintype "passive"))
      (node (ref "VT9") (pin "3") (pinfunction "D_3") (pintype "passive"))
    )
    (net (code "3") (name "/ADC1") (class "Default")
      (node (ref "C10") (pin "1") (pinfunction "1_1") (pintype "passive"))
      (node (ref "D1") (pin "47") (pinfunction "ADC1_47") (pintype "input"))
      (node (ref "R18") (pin "2") (pinfunction "CW_2") (pintype "passive"))
      (node (ref "R19") (pin "1") (pinfunction "CCW_1") (pintype "passive"))
      (node (ref "TP1") (pin "1") (pinfunction "1_1") (pintype "passive"))
      (node (ref "VT1") (pin "3") (pinfunction "D_3") (pintype "passive"))
    )
    (net (code "4") (name "/ADC2") (class "Default")
      (node (ref "D1") (pin "46") (pinfunction "ADC2_46") (pintype "input"))
      (node (ref "R33") (pin "1") (pinfunction "CCW_1") (pintype "passive"))
      (node (ref "R34") (pin "2") (pinfunction "CW_2") (pintype "passive"))
    )
    (net (code "5") (name "/AUX_ANT") (class "Default")
      (node (ref "D1") (pin "59") (pinfunction "AUX_ANT_59") (pintype "input"))
      (node (ref "VD10") (pin "2") (pinfunction "K_2") (pintype "passive"))
      (node (ref "X9") (pin "1") (pinfunction "SIG_1") (pintype "bidirectional"))
    )
    (net (code "6") (name "/BAK_ON") (class "Default")
      (node (ref "R33") (pin "2") (pinfunction "CW_2") (pintype "passive"))
    )
    (net (code "7") (name "/BOOT") (class "Default")
      (node (ref "D1") (pin "85") (pinfunction "BOOT_CFG0_85") (pintype "input"))
      (node (ref "VD9") (pin "2") (pinfunction "NEG_2") (pintype "passive"))
      (node (ref "X6") (pin "1") (pinfunction "1_1") (pintype "passive"))
    )
    (net (code "8") (name "/FLIGHT") (class "Default")
      (node (ref "D1") (pin "54") (pinfunction "FLIGHTMODE_54") (pintype "input"))
      (node (ref "R31") (pin "1") (pinfunction "CCW_1") (pintype "passive"))
    )
    (net (code "9") (name "/GNSS_ANT") (class "Default")
      (node (ref "C41") (pin "2") (pinfunction "2_2") (pintype "passive"))
      (node (ref "D1") (pin "79") (pinfunction "GNSS_ANT_79") (pintype "bidirectional"))
    )
    (net (code "10") (name "/GPIO6") (class "Default")
      (node (ref "D1") (pin "34") (pinfunction "GPIO6_34") (pintype "bidirectional"))
      (node (ref "R9") (pin "1") (pinfunction "CCW_1") (pintype "passive"))
    )
    (net (code "11") (name "/GPIO26") (class "Default")
      (node (ref "D1") (pin "48") (pinfunction "SD_DET_48") (pintype "bidirectional"))
      (node (ref "R13") (pin "1") (pinfunction "CCW_1") (pintype "passive"))
    )
    (net (code "12") (name "/GPIO41") (class "Default")
      (node (ref "D1") (pin "52") (pinfunction "GPIO41_52") (pintype "bidirectional"))
      (node (ref "R36") (pin "1") (pinfunction "CCW_1") (pintype "passive"))
    )
    (net (code "13") (name "/GPIO43") (class "Default")
      (node (ref "D1") (pin "50") (pinfunction "GPIO43_50") (pintype "bidirectional"))
      (node (ref "R73") (pin "1") (pinfunction "CCW_1") (pintype "passive"))
    )
    (net (code "14") (name "/GPIO52") (class "Default")
      (node (ref "D1") (pin "49") (pinfunction "STATUS_49") (pintype "output"))
      (node (ref "R11") (pin "1") (pinfunction "CCW_1") (pintype "passive"))
    )
    (net (code "15") (name "/GPIO77") (class "Default")
      (node (ref "D1") (pin "87") (pinfunction "GPIO77_87") (pintype "bidirectional"))
    )
    (net (code "16") (name "/I2C_SCL") (class "Default")
      (node (ref "D1") (pin "55") (pinfunction "SCL_55") (pintype "output"))
      (node (ref "D2") (pin "11") (pinfunction "SCLK_11") (pintype "passive"))
      (node (ref "R20") (pin "1") (pinfunction "CCW_1") (pintype "passive"))
      (node (ref "TP4") (pin "1") (pinfunction "1_1") (pintype "passive"))
      (node (ref "VT8") (pin "2") (pinfunction "S_2") (pintype "passive"))
    )
    (net (code "17") (name "/I2C_SDA") (class "Default")
      (node (ref "D1") (pin "56") (pinfunction "SDA_56") (pintype "bidirectional"))
      (node (ref "D2") (pin "12") (pinfunction "SDIO_12") (pintype "passive"))
      (node (ref "R21") (pin "1") (pinfunction "CCW_1") (pintype "passive"))
      (node (ref "TP5") (pin "1") (pinfunction "1_1") (pintype "passive"))
      (node (ref "VT9") (pin "2") (pinfunction "S_2") (pintype "passive"))
    )
    (net (code "18") (name "/LCD_BCKLT") (class "Default")
      (node (ref "R75") (pin "1") (pinfunction "CCW_1") (pintype "passive"))
      (node (ref "VT10") (pin "3") (pinfunction "D_3") (pintype "passive"))
    )
    (net (code "19") (name "/LCD_D4") (class "Default")
      (node (ref "D8") (pin "9") (pinfunction "P4_9") (pintype "bidirectional"))
      (node (ref "X7") (pin "2") (pinfunction "2_2") (pintype "passive"))
    )
    (net (code "20") (name "/LCD_D5") (class "Default")
      (node (ref "D8") (pin "10") (pinfunction "P5_10") (pintype "bidirectional"))
      (node (ref "X7") (pin "4") (pinfunction "4_4") (pintype "passive"))
    )
    (net (code "21") (name "/LCD_D6") (class "Default")
      (node (ref "D8") (pin "11") (pinfunction "P6_11") (pintype "bidirectional"))
      (node (ref "X7") (pin "6") (pinfunction "6_6") (pintype "passive"))
    )
    (net (code "22") (name "/LCD_D7") (class "Default")
      (node (ref "D8") (pin "12") (pinfunction "P7_12") (pintype "bidirectional"))
      (node (ref "X7") (pin "8") (pinfunction "8_8") (pintype "passive"))
    )
    (net (code "23") (name "/LCD_E") (class "Default")
      (node (ref "D8") (pin "6") (pinfunction "P2_6") (pintype "bidirectional"))
      (node (ref "X7") (pin "5") (pinfunction "5_5") (pintype "passive"))
    )
    (net (code "24") (name "/LCD_K") (class "Default")
      (node (ref "VT11") (pin "3") (pinfunction "D_3") (pintype "passive"))
      (node (ref "X7") (pin "11") (pinfunction "11_11") (pintype "passive"))
    )
    (net (code "25") (name "/LCD_RS") (class "Default")
      (node (ref "D8") (pin "4") (pinfunction "P0_4") (pintype "bidirectional"))
      (node (ref "X7") (pin "9") (pinfunction "9_9") (pintype "passive"))
    )
    (net (code "26") (name "/LCD_RW") (class "Default")
      (node (ref "D8") (pin "5") (pinfunction "P1_5") (pintype "bidirectional"))
      (node (ref "X7") (pin "7") (pinfunction "7_7") (pintype "passive"))
    )
    (net (code "27") (name "/LCD_V0") (class "Default")
      (node (ref "R83") (pin "1") (pinfunction "CCW_1") (pintype "passive"))
      (node (ref "R84") (pin "1") (pinfunction "CCW_1") (pintype "passive"))
      (node (ref "X7") (pin "13") (pinfunction "13_13") (pintype "passive"))
    )
    (net (code "28") (name "/MAIN_ANT") (class "Default")
      (node (ref "D1") (pin "82") (pinfunction "MAIN_ANT_82") (pintype "bidirectional"))
      (node (ref "R44") (pin "1") (pinfunction "CCW_1") (pintype "passive"))
    )
    (net (code "29") (name "/MCLK") (class "Default")
      (node (ref "C21") (pin "2") (pinfunction "2_2") (pintype "passive"))
      (node (ref "D2") (pin "10") (pinfunction "MCLK_10") (pintype "passive"))
      (node (ref "R25") (pin "2") (pinfunction "CW_2") (pintype "passive"))
      (node (ref "R78") (pin "2") (pinfunction "CW_2") (pintype "passive"))
    )
    (net (code "30") (name "/MICBIAS") (class "Default")
      (node (ref "C24") (pin "2") (pinfunction "2_2") (pintype "passive"))
      (node (ref "D2") (pin "1") (pinfunction "MICBIAS_1") (pintype "passive"))
      (node (ref "R17") (pin "1") (pinfunction "CCW_1") (pintype "passive"))
    )
    (net (code "31") (name "/MIC_N") (class "Default")
      (node (ref "C23") (pin "1") (pinfunction "1_1") (pintype "passive"))
      (node (ref "C6") (pin "2") (pinfunction "2_2") (pintype "passive"))
      (node (ref "C8") (pin "1") (pinfunction "1_1") (pintype "passive"))
      (node (ref "R26") (pin "1") (pinfunction "CCW_1") (pintype "passive"))
    )
    (net (code "32") (name "/MIC_P") (class "Default")
      (node (ref "C22") (pin "1") (pinfunction "1_1") (pintype "passive"))
      (node (ref "IND1") (pin "1") (pinfunction "1_1") (pintype "passive"))
      (node (ref "R17") (pin "2") (pinfunction "CW_2") (pintype "passive"))
      (node (ref "VT1") (pin "1") (pinfunction "G_1") (pintype "passive"))
    )
    (net (code "33") (name "/MOUT") (class "Default")
      (node (ref "C30") (pin "1") (pinfunction "1_1") (pintype "passive"))
      (node (ref "R69") (pin "1") (pinfunction "CCW_1") (pintype "passive"))
    )
    (net (code "34") (name "/NETLIGHT") (class "Default")
      (node (ref "D1") (pin "51") (pinfunction "NETLIGHT_51") (pintype "output"))
      (node (ref "R27") (pin "1") (pinfunction "CCW_1") (pintype "passive"))
    )
    (net (code "35") (name "/OCLK") (class "Default")
      (node (ref "D3") (pin "1") (pinfunction "B2_1") (pintype "bidirectional"))
      (node (ref "D7") (pin "5") (pinfunction "CLKOUT_5") (pintype "output"))
    )
    (net (code "36") (name "/PA4") (class "Default")
      (node (ref "R12") (pin "1") (pinfunction "CCW_1") (pintype "passive"))
    )
    (net (code "37") (name "/PB0") (class "Default")
      (node (ref "R10") (pin "1") (pinfunction "CCW_1") (pintype "passive"))
    )
    (net (code "38") (name "/PB2") (class "Default")
      (node (ref "R8") (pin "1") (pinfunction "CCW_1") (pintype "passive"))
    )
    (net (code "39") (name "/PCM_CLK") (class "Default")
      (node (ref "D1") (pin "76") (pinfunction "PCM_CLK_76") (pintype "output"))
      (node (ref "D2") (pin "9") (pinfunction "BCLK_9") (pintype "passive"))
      (node (ref "D3") (pin "5") (pinfunction "A1_5") (pintype "bidirectional"))
      (node (ref "R25") (pin "1") (pinfunction "CCW_1") (pintype "passive"))
    )
    (net (code "40") (name "/PCM_IN") (class "Default")
      (node (ref "D1") (pin "74") (pinfunction "PCM_IN_74") (pintype "input"))
      (node (ref "D2") (pin "6") (pinfunction "ADCOUT_6") (pintype "passive"))
    )
    (net (code "41") (name "/PCM_OUT") (class "Default")
      (node (ref "D1") (pin "73") (pinfunction "PCM_OUT_73") (pintype "output"))
      (node (ref "D2") (pin "7") (pinfunction "DACIN_7") (pintype "passive"))
    )
    (net (code "42") (name "/PCM_SYNC") (class "Default")
      (node (ref "D1") (pin "75") (pinfunction "PCM_SYNC_75") (pintype "output"))
      (node (ref "D2") (pin "8") (pinfunction "FS_8") (pintype "passive"))
    )
    (net (code "43") (name "/PWRKEY") (class "Default")
      (node (ref "D1") (pin "3") (pinfunction "PWRKEY_3") (pintype "input"))
      (node (ref "R32") (pin "1") (pinfunction "CCW_1") (pintype "passive"))
      (node (ref "S5") (pin "1") (pinfunction "1_1") (pintype "passive"))
      (node (ref "VD17") (pin "2") (pinfunction "NEG_2") (pintype "passive"))
    )
    (net (code "44") (name "/RESET") (class "Default")
      (node (ref "C35") (pin "1") (pinfunction "1_1") (pintype "passive"))
      (node (ref "D1") (pin "4") (pinfunction "RESET_4") (pintype "input"))
      (node (ref "TP6") (pin "1") (pinfunction "1_1") (pintype "passive"))
      (node (ref "VD8") (pin "2") (pinfunction "NEG_2") (pintype "passive"))
    )
    (net (code "45") (name "/SD_CLK") (class "Default")
      (node (ref "D1") (pin "26") (pinfunction "SD_CLK_26") (pintype "output"))
      (node (ref "VD5") (pin "4") (pinfunction "B_4") (pintype "passive"))
      (node (ref "X2") (pin "5") (pinfunction "CLK_5") (pintype "input"))
    )
    (net (code "46") (name "/SD_CMD") (class "Default")
      (node (ref "D1") (pin "21") (pinfunction "SD_CMD_21") (pintype "output"))
      (node (ref "VD18") (pin "5") (pinfunction "D_5") (pintype "passive"))
      (node (ref "X2") (pin "3") (pinfunction "CMD_3") (pintype "input"))
    )
    (net (code "47") (name "/SD_D0") (class "Default")
      (node (ref "D1") (pin "22") (pinfunction "SD_DATA0_22") (pintype "bidirectional"))
      (node (ref "VD18") (pin "3") (pinfunction "C_3") (pintype "passive"))
      (node (ref "X2") (pin "7") (pinfunction "D0_7") (pintype "bidirectional"))
    )
    (net (code "48") (name "/SD_D1") (class "Default")
      (node (ref "D1") (pin "23") (pinfunction "SD_DATA1_23") (pintype "bidirectional"))
      (node (ref "VD18") (pin "4") (pinfunction "B_4") (pintype "passive"))
      (node (ref "X2") (pin "8") (pinfunction "D1_8") (pintype "bidirectional"))
    )
    (net (code "49") (name "/SD_D2") (class "Default")
      (node (ref "D1") (pin "24") (pinfunction "SD_DATA2_24") (pintype "bidirectional"))
      (node (ref "VD5") (pin "3") (pinfunction "C_3") (pintype "passive"))
      (node (ref "X2") (pin "1") (pinfunction "D2_1") (pintype "bidirectional"))
    )
    (net (code "50") (name "/SD_D3") (class "Default")
      (node (ref "D1") (pin "25") (pinfunction "SD_DATA3_25") (pintype "bidirectional"))
      (node (ref "VD5") (pin "5") (pinfunction "D_5") (pintype "passive"))
      (node (ref "X2") (pin "2") (pinfunction "D3_2") (pintype "bidirectional"))
    )
    (net (code "51") (name "/SPEAKER") (class "Default")
      (node (ref "C38") (pin "2") (pinfunction "2_2") (pintype "passive"))
      (node (ref "C39") (pin "2") (pinfunction "2_2") (pintype "passive"))
      (node (ref "C40") (pin "1") (pinfunction "1_1") (pintype "passive"))
      (node (ref "X8") (pin "2") (pinfunction "2_2") (pintype "passive"))
    )
    (net (code "52") (name "/UART_RX") (class "Default")
      (node (ref "D1") (pin "68") (pinfunction "RXD_68") (pintype "input"))
    )
    (net (code "53") (name "/UART_TX") (class "Default")
      (node (ref "D1") (pin "71") (pinfunction "TXD_71") (pintype "output"))
    )
    (net (code "54") (name "/USB_N") (class "Default")
      (node (ref "D1") (pin "12") (pinfunction "USB_DN_12") (pintype "bidirectional"))
      (node (ref "VD2") (pin "2") (pinfunction "NEG_2") (pintype "passive"))
      (node (ref "X3") (pin "2") (pinfunction "D-_2") (pintype "passive"))
    )
    (net (code "55") (name "/USB_P") (class "Default")
      (node (ref "D1") (pin "13") (pinfunction "USB_DP_13") (pintype "bidirectional"))
      (node (ref "VD4") (pin "2") (pinfunction "NEG_2") (pintype "passive"))
      (node (ref "X3") (pin "3") (pinfunction "D+_3") (pintype "passive"))
    )
    (net (code "56") (name "/USIM_CLK") (class "Default")
      (node (ref "D1") (pin "19") (pinfunction "USIM_CLK_19") (pintype "output"))
      (node (ref "R15") (pin "1") (pinfunction "CCW_1") (pintype "passive"))
    )
    (net (code "57") (name "/USIM_DATA") (class "Default")
      (node (ref "D1") (pin "17") (pinfunction "USIM_DATA_17") (pintype "bidirectional"))
      (node (ref "R16") (pin "1") (pinfunction "CCW_1") (pintype "passive"))
    )
    (net (code "58") (name "/USIM_DET") (class "Default")
      (node (ref "D1") (pin "53") (pinfunction "USIM_DET_53") (pintype "bidirectional"))
    )
    (net (code "59") (name "/USIM_RST") (class "Default")
      (node (ref "D1") (pin "18") (pinfunction "USIM_RST_18") (pintype "output"))
      (node (ref "R14") (pin "1") (pinfunction "CCW_1") (pintype "passive"))
    )
    (net (code "60") (name "/USIM_VDD") (class "Default")
      (node (ref "C3") (pin "1") (pinfunction "1_1") (pintype "passive"))
      (node (ref "D1") (pin "20") (pinfunction "USIM_VDD_20") (pintype "output"))
      (node (ref "VD1") (pin "6") (pinfunction "C5_6") (pintype "passive"))
      (node (ref "X1") (pin "C1") (pinfunction "VCC_C1") (pintype "input"))
    )
    (net (code "61") (name "1V8") (class "Default")
      (node (ref "C33") (pin "2") (pinfunction "2_2") (pintype "passive"))
      (node (ref "D1") (pin "15") (pinfunction "VDD_1V8_15") (pintype "power_in"))
      (node (ref "D3") (pin "3") (pinfunction "VCCA_3") (pintype "power_in"))
      (node (ref "D3") (pin "6") (pinfunction "OE_6") (pintype "input"))
      (node (ref "IND3") (pin "1") (pinfunction "1_1") (pintype "passive"))
      (node (ref "R1") (pin "2") (pinfunction "CW_2") (pintype "passive"))
      (node (ref "R18") (pin "1") (pinfunction "CCW_1") (pintype "passive"))
      (node (ref "R20") (pin "2") (pinfunction "CW_2") (pintype "passive"))
      (node (ref "R21") (pin "2") (pinfunction "CW_2") (pintype "passive"))
      (node (ref "R31") (pin "2") (pinfunction "CW_2") (pintype "passive"))
      (node (ref "R35") (pin "1") (pinfunction "CCW_1") (pintype "passive"))
      (node (ref "TP2") (pin "1") (pinfunction "1_1") (pintype "passive"))
      (node (ref "VT8") (pin "1") (pinfunction "G_1") (pintype "passive"))
      (node (ref "VT9") (pin "1") (pinfunction "G_1") (pintype "passive"))
    )
    (net (code "62") (name "3V") (class "Default")
      (node (ref "C1") (pin "2") (pinfunction "2_2") (pintype "passive"))
      (node (ref "C2") (pin "2") (pinfunction "2_2") (pintype "passive"))
      (node (ref "X2") (pin "4") (pinfunction "VDD_4") (pintype "passive"))
    )
    (net (code "63") (name "3V3") (class "Default")
      (node (ref "C80") (pin "1") (pinfunction "1_1") (pintype "passive"))
      (node (ref "C81") (pin "2") (pinfunction "2_2") (pintype "passive"))
      (node (ref "D3") (pin "7") (pinfunction "VCCB_7") (pintype "power_in"))
      (node (ref "D7") (pin "2") (pinfunction "VDD_2") (pintype "passive"))
      (node (ref "IND2") (pin "1") (pinfunction "1_1") (pintype "passive"))
      (node (ref "IND4") (pin "1") (pinfunction "1_1") (pintype "passive"))
      (node (ref "R45") (pin "2") (pinfunction "CW_2") (pintype "passive"))
      (node (ref "R71") (pin "1") (pinfunction "CCW_1") (pintype "passive"))
      (node (ref "R72") (pin "1") (pinfunction "CCW_1") (pintype "passive"))
    )
    (net (code "64") (name "3V8_BAK") (class "Default")
      (node (ref "IND6") (pin "2") (pinfunction "2_2") (pintype "passive"))
      (node (ref "VD7") (pin "C") (pinfunction "NEG_C") (pintype "passive"))
    )
    (net (code "65") (name "3V8_EXT") (class "Default")
      (node (ref "HL1") (pin "1") (pinfunction "POS_1") (pintype "passive"))
      (node (ref "HL2") (pin "1") (pinfunction "POS_1") (pintype "passive"))
    )
    (net (code "66") (name "5V") (class "Default")
      (node (ref "IND9") (pin "1") (pinfunction "1_1") (pintype "passive"))
      (node (ref "R29") (pin "1") (pinfunction "CCW_1") (pintype "passive"))
      (node (ref "R39") (pin "2") (pinfunction "CW_2") (pintype "passive"))
      (node (ref "R75") (pin "2") (pinfunction "CW_2") (pintype "passive"))
    )
    (net (code "67") (name "5V_LCD") (class "Default")
      (node (ref "C78") (pin "1") (pinfunction "1_1") (pintype "passive"))
      (node (ref "C79") (pin "2") (pinfunction "2_2") (pintype "passive"))
      (node (ref "C82") (pin "1") (pinfunction "1_1") (pintype "passive"))
      (node (ref "D8") (pin "16") (pinfunction "VDD_16") (pintype "power_in"))
      (node (ref "IND9") (pin "2") (pinfunction "2_2") (pintype "passive"))
      (node (ref "R79") (pin "2") (pinfunction "CW_2") (pintype "passive"))
      (node (ref "R80") (pin "2") (pinfunction "CW_2") (pintype "passive"))
      (node (ref "R81") (pin "2") (pinfunction "CW_2") (pintype "passive"))
      (node (ref "R82") (pin "1") (pinfunction "CCW_1") (pintype "passive"))
      (node (ref "R83") (pin "2") (pinfunction "CW_2") (pintype "passive"))
      (node (ref "X7") (pin "1") (pinfunction "1_1") (pintype "passive"))
      (node (ref "X7") (pin "3") (pinfunction "3_3") (pintype "passive"))
    )
    (net (code "68") (name "5V_USB") (class "Default")
      (node (ref "D1") (pin "11") (pinfunction "USB_VBUS_11") (pintype "input"))
      (node (ref "VD3") (pin "2") (pinfunction "NEG_2") (pintype "passive"))
      (node (ref "X3") (pin "1") (pinfunction "VCC_1") (pintype "power_in"))
    )
    (net (code "69") (name "AGND") (class "Default")
      (node (ref "C11") (pin "2") (pinfunction "2_2") (pintype "passive"))
      (node (ref "C12") (pin "2") (pinfunction "2_2") (pintype "passive"))
      (node (ref "C13") (pin "2") (pinfunction "2_2") (pintype "passive"))
      (node (ref "C14") (pin "2") (pinfunction "2_2") (pintype "passive"))
      (node (ref "C15") (pin "2") (pinfunction "2_2") (pintype "passive"))
      (node (ref "C16") (pin "2") (pinfunction "2_2") (pintype "passive"))
      (node (ref "C17") (pin "2") (pinfunction "2_2") (pintype "passive"))
      (node (ref "C18") (pin "2") (pinfunction "2_2") (pintype "passive"))
      (node (ref "C19") (pin "2") (pinfunction "2_2") (pintype "passive"))
      (node (ref "C20") (pin "2") (pinfunction "2_2") (pintype "passive"))
      (node (ref "C21") (pin "1") (pinfunction "1_1") (pintype "passive"))
      (node (ref "C24") (pin "1") (pinfunction "1_1") (pintype "passive"))
      (node (ref "C28") (pin "1") (pinfunction "1_1") (pintype "passive"))
      (node (ref "C29") (pin "1") (pinfunction "1_1") (pintype "passive"))
      (node (ref "C32") (pin "2") (pinfunction "2_2") (pintype "passive"))
      (node (ref "C33") (pin "1") (pinfunction "1_1") (pintype "passive"))
      (node (ref "C34") (pin "2") (pinfunction "2_2") (pintype "passive"))
      (node (ref "C4") (pin "2") (pinfunction "2_2") (pintype "passive"))
      (node (ref "C6") (pin "1") (pinfunction "1_1") (pintype "passive"))
      (node (ref "C8") (pin "2") (pinfunction "2_2") (pintype "passive"))
      (node (ref "C80") (pin "2") (pinfunction "2_2") (pintype "passive"))
      (node (ref "C81") (pin "1") (pinfunction "1_1") (pintype "passive"))
      (node (ref "D2") (pin "15") (pinfunction "VSSSPK_15") (pintype "passive"))
      (node (ref "D2") (pin "21") (pinfunction "VSSA_PAD_21") (pintype "passive"))
      (node (ref "D2") (pin "3") (pinfunction "VSSA_3") (pintype "passive"))
      (node (ref "D2") (pin "5") (pinfunction "VSSD_5") (pintype "passive"))
      (node (ref "D3") (pin "2") (pinfunction "GND_2") (pintype "power_in"))
      (node (ref "D7") (pin "3") (pinfunction "GND_3") (pintype "passive"))
      (node (ref "D7") (pin "6") (pinfunction "S0_6") (pintype "passive"))
      (node (ref "DA1") (pin "3") (pinfunction "GND_3") (pintype "power_in"))
      (node (ref "IND5") (pin "1") (pinfunction "1_1") (pintype "passive"))
      (node (ref "R2") (pin "1") (pinfunction "CCW_1") (pintype "passive"))
      (node (ref "R26") (pin "2") (pinfunction "CW_2") (pintype "passive"))
      (node (ref "R42") (pin "2") (pinfunction "CW_2") (pintype "passive"))
      (node (ref "R43") (pin "2") (pinfunction "CW_2") (pintype "passive"))
      (node (ref "R70") (pin "2") (pinfunction "CW_2") (pintype "passive"))
      (node (ref "X4") (pin "1") (pinfunction "1_1") (pintype "passive"))
      (node (ref "X8") (pin "1") (pinfunction "1_1") (pintype "passive"))
    )
    (net (code "70") (name "AUX_GND") (class "Default")
      (node (ref "D1") (pin "58") (pinfunction "GND_58") (pintype "power_in"))
      (node (ref "D1") (pin "60") (pinfunction "GND_60") (pintype "power_in"))
      (node (ref "R23") (pin "2") (pinfunction "CW_2") (pintype "passive"))
      (node (ref "VD10") (pin "1") (pinfunction "A_1") (pintype "passive"))
      (node (ref "X9") (pin "2") (pinfunction "GND_2") (pintype "power_in"))
      (node (ref "X9") (pin "3") (pinfunction "GND_3") (pintype "power_in"))
    )
    (net (code "71") (name "GND") (class "Default")
      (node (ref "C1") (pin "1") (pinfunction "1_1") (pintype "passive"))
      (node (ref "C10") (pin "2") (pinfunction "2_2") (pintype "passive"))
      (node (ref "C2") (pin "1") (pinfunction "1_1") (pintype "passive"))
      (node (ref "C25") (pin "2") (pinfunction "2_2") (pintype "passive"))
      (node (ref "C26") (pin "2") (pinfunction "-_2") (pintype "passive"))
      (node (ref "C27") (pin "2") (pinfunction "-_2") (pintype "passive"))
      (node (ref "C3") (pin "2") (pinfunction "2_2") (pintype "passive"))
      (node (ref "C35") (pin "2") (pinfunction "2_2") (pintype "passive"))
      (node (ref "C5") (pin "2") (pinfunction "2_2") (pintype "passive"))
      (node (ref "C7") (pin "2") (pinfunction "2_2") (pintype "passive"))
      (node (ref "C78") (pin "2") (pinfunction "2_2") (pintype "passive"))
      (node (ref "C79") (pin "1") (pinfunction "1_1") (pintype "passive"))
      (node (ref "C82") (pin "2") (pinfunction "2_2") (pintype "passive"))
      (node (ref "C9") (pin "2") (pinfunction "2_2") (pintype "passive"))
      (node (ref "D1") (pin "1") (pinfunction "GND_1") (pintype "power_in"))
      (node (ref "D1") (pin "10") (pinfunction "GND_10") (pintype "power_in"))
      (node (ref "D1") (pin "14") (pinfunction "GND_14") (pintype "power_in"))
      (node (ref "D1") (pin "2") (pinfunction "GND_2") (pintype "power_in"))
      (node (ref "D1") (pin "37") (pinfunction "GND_37") (pintype "power_in"))
      (node (ref "D1") (pin "40") (pinfunction "GND_40") (pintype "power_in"))
      (node (ref "D1") (pin "43") (pinfunction "GND_43") (pintype "power_in"))
      (node (ref "D1") (pin "5") (pinfunction "GND_5") (pintype "power_in"))
      (node (ref "D1") (pin "57") (pinfunction "GND_57") (pintype "power_in"))
      (node (ref "D1") (pin "61") (pinfunction "GND_61") (pintype "power_in"))
      (node (ref "D1") (pin "64") (pinfunction "GND_64") (pintype "power_in"))
      (node (ref "D1") (pin "65") (pinfunction "GND_65") (pintype "power_in"))
      (node (ref "D1") (pin "77") (pinfunction "GND_77") (pintype "power_in"))
      (node (ref "D1") (pin "81") (pinfunction "GND_81") (pintype "power_in"))
      (node (ref "D8") (pin "8") (pinfunction "VSS_8") (pintype "passive"))
      (node (ref "IND5") (pin "2") (pinfunction "2_2") (pintype "passive"))
      (node (ref "R19") (pin "2") (pinfunction "CW_2") (pintype "passive"))
      (node (ref "R22") (pin "1") (pinfunction "CCW_1") (pintype "passive"))
      (node (ref "R23") (pin "1") (pinfunction "CCW_1") (pintype "passive"))
      (node (ref "R24") (pin "1") (pinfunction "CCW_1") (pintype "passive"))
      (node (ref "R28") (pin "1") (pinfunction "CCW_1") (pintype "passive"))
      (node (ref "R32") (pin "2") (pinfunction "CW_2") (pintype "passive"))
      (node (ref "R34") (pin "1") (pinfunction "CCW_1") (pintype "passive"))
      (node (ref "R38") (pin "1") (pinfunction "CCW_1") (pintype "passive"))
      (node (ref "R74") (pin "1") (pinfunction "CCW_1") (pintype "passive"))
      (node (ref "R84") (pin "2") (pinfunction "CW_2") (pintype "passive"))
      (node (ref "S1") (pin "2") (pinfunction "2_2") (pintype "passive"))
      (node (ref "S1") (pin "SH") (pinfunction "SHLD_SH") (pintype "passive"))
      (node (ref "S2") (pin "2") (pinfunction "2_2") (pintype "passive"))
      (node (ref "S2") (pin "SH") (pinfunction "SHLD_SH") (pintype "passive"))
      (node (ref "S3") (pin "2") (pinfunction "2_2") (pintype "passive"))
      (node (ref "S3") (pin "SH") (pinfunction "SHLD_SH") (pintype "passive"))
      (node (ref "S5") (pin "2") (pinfunction "2_2") (pintype "passive"))
      (node (ref "S5") (pin "SH") (pinfunction "SHLD_SH") (pintype "passive"))
      (node (ref "TP7") (pin "1") (pinfunction "1_1") (pintype "passive"))
      (node (ref "VD1") (pin "2") (pinfunction "A_2") (pintype "passive"))
      (node (ref "VD17") (pin "1") (pinfunction "POS_1") (pintype "passive"))
      (node (ref "VD18") (pin "2") (pinfunction "GND_2") (pintype "passive"))
      (node (ref "VD2") (pin "1") (pinfunction "POS_1") (pintype "passive"))
      (node (ref "VD3") (pin "1") (pinfunction "POS_1") (pintype "passive"))
      (node (ref "VD4") (pin "1") (pinfunction "POS_1") (pintype "passive"))
      (node (ref "VD5") (pin "2") (pinfunction "GND_2") (pintype "passive"))
      (node (ref "VD6") (pin "1") (pinfunction "GND_1") (pintype "passive"))
      (node (ref "VD7") (pin "A") (pinfunction "POS_A") (pintype "passive"))
      (node (ref "VD8") (pin "1") (pinfunction "POS_1") (pintype "passive"))
      (node (ref "VD9") (pin "1") (pinfunction "POS_1") (pintype "passive"))
      (node (ref "VT1") (pin "2") (pinfunction "S_2") (pintype "passive"))
      (node (ref "VT10") (pin "2") (pinfunction "S_2") (pintype "passive"))
      (node (ref "VT11") (pin "2") (pinfunction "S_2") (pintype "passive"))
      (node (ref "VT2") (pin "2") (pinfunction "E_2") (pintype "passive"))
      (node (ref "VT3") (pin "2") (pinfunction "E_2") (pintype "passive"))
      (node (ref "X1") (pin "C5") (pinfunction "GND_C5") (pintype "passive"))
      (node (ref "X1") (pin "SHLD") (pinfunction "SHLD_SHLD") (pintype "passive"))
      (node (ref "X2") (pin "10") (pinfunction "SHLD_10") (pintype "passive"))
      (node (ref "X2") (pin "11") (pinfunction "SHLD_11") (pintype "passive"))
      (node (ref "X2") (pin "12") (pinfunction "SHLD_12") (pintype "passive"))
      (node (ref "X2") (pin "13") (pinfunction "SHLD_13") (pintype "passive"))
      (node (ref "X2") (pin "6") (pinfunction "GND_6") (pintype "passive"))
      (node (ref "X3") (pin "5") (pinfunction "GND_5") (pintype "power_in"))
      (node (ref "X3") (pin "SH1") (pinfunction "SHIELD_SH1") (pintype "passive"))
      (node (ref "X3") (pin "SH2") (pinfunction "SHIELD_SH2") (pintype "passive"))
      (node (ref "X3") (pin "SH4") (pinfunction "SHIELD_SH4") (pintype "passive"))
      (node (ref "X3") (pin "SH5") (pinfunction "SHIELD_SH5") (pintype "passive"))
      (node (ref "X3") (pin "SH6") (pinfunction "SHIELD_SH6") (pintype "passive"))
      (node (ref "X3") (pin "SH7") (pinfunction "SHIELD_SH7") (pintype "passive"))
      (node (ref "X7") (pin "12") (pinfunction "12_12") (pintype "passive"))
      (node (ref "X7") (pin "14") (pinfunction "14_14") (pintype "passive"))
    )
    (net (code "72") (name "GNSS_GND") (class "Default")
      (node (ref "C44") (pin "1") (pinfunction "1_1") (pintype "passive"))
      (node (ref "D1") (pin "78") (pinfunction "GND_78") (pintype "power_in"))
      (node (ref "D1") (pin "80") (pinfunction "GND_80") (pintype "power_in"))
      (node (ref "R24") (pin "2") (pinfunction "CW_2") (pintype "passive"))
      (node (ref "X10") (pin "G") (pinfunction "GND_G") (pintype "power_in"))
    )
    (net (code "73") (name "MAIN_GND") (class "Default")
      (node (ref "ANT1") (pin "2") (pinfunction "GND_2") (pintype "power_in"))
      (node (ref "C42") (pin "1") (pinfunction "1_1") (pintype "passive"))
      (node (ref "C43") (pin "1") (pinfunction "1_1") (pintype "passive"))
      (node (ref "D1") (pin "41") (pinfunction "GND_41") (pintype "power_in"))
      (node (ref "R22") (pin "2") (pinfunction "CW_2") (pintype "passive"))
    )
    (net (code "74") (name "Net-(ANT1-FEEDING)") (class "Default")
      (node (ref "ANT1") (pin "3") (pinfunction "FEEDING_3") (pintype "passive"))
      (node (ref "C42") (pin "2") (pinfunction "2_2") (pintype "passive"))
      (node (ref "C43") (pin "2") (pinfunction "2_2") (pintype "passive"))
      (node (ref "R44") (pin "2") (pinfunction "CW_2") (pintype "passive"))
    )
    (net (code "75") (name "Net-(C26-+)") (class "Default")
      (node (ref "C25") (pin "1") (pinfunction "1_1") (pintype "passive"))
      (node (ref "C26") (pin "1") (pinfunction "+_1") (pintype "passive"))
      (node (ref "C27") (pin "1") (pinfunction "+_1") (pintype "passive"))
      (node (ref "D1") (pin "38") (pinfunction "VBAT_38") (pintype "power_in"))
      (node (ref "D1") (pin "39") (pinfunction "VBAT_39") (pintype "power_in"))
      (node (ref "IND6") (pin "1") (pinfunction "1_1") (pintype "passive"))
    )
    (net (code "76") (name "Net-(C31-+)") (class "Default")
      (node (ref "C31") (pin "1") (pinfunction "+_1") (pintype "passive"))
      (node (ref "IND7") (pin "1") (pinfunction "1_1") (pintype "passive"))
    )
    (net (code "77") (name "Net-(C31--)") (class "Default")
      (node (ref "C31") (pin "2") (pinfunction "-_2") (pintype "passive"))
      (node (ref "R69") (pin "2") (pinfunction "CW_2") (pintype "passive"))
      (node (ref "R70") (pin "1") (pinfunction "CCW_1") (pintype "passive"))
      (node (ref "TP3") (pin "1") (pinfunction "1_1") (pintype "passive"))
    )
    (net (code "78") (name "Net-(D1-VBAT-Pad62)") (class "Default")
      (node (ref "D1") (pin "62") (pinfunction "VBAT_62") (pintype "power_in"))
      (node (ref "D1") (pin "63") (pinfunction "VBAT_63") (pintype "power_in"))
    )
    (net (code "79") (name "Net-(D2-MIC+)") (class "Default")
      (node (ref "C22") (pin "2") (pinfunction "2_2") (pintype "passive"))
      (node (ref "D2") (pin "20") (pinfunction "MIC+_20") (pintype "passive"))
    )
    (net (code "80") (name "Net-(D2-MIC-)") (class "Default")
      (node (ref "C23") (pin "2") (pinfunction "2_2") (pintype "passive"))
      (node (ref "D2") (pin "19") (pinfunction "MIC-_19") (pintype "passive"))
    )
    (net (code "81") (name "Net-(D2-MOUT)") (class "Default")
      (node (ref "C29") (pin "2") (pinfunction "2_2") (pintype "passive"))
      (node (ref "C30") (pin "2") (pinfunction "2_2") (pintype "passive"))
      (node (ref "D2") (pin "13") (pinfunction "MOUT_13") (pintype "passive"))
    )
    (net (code "82") (name "Net-(D2-VDDA)") (class "Default")
      (node (ref "C11") (pin "1") (pinfunction "1_1") (pintype "passive"))
      (node (ref "C14") (pin "1") (pinfunction "1_1") (pintype "passive"))
      (node (ref "C17") (pin "1") (pinfunction "1_1") (pintype "passive"))
      (node (ref "C19") (pin "1") (pinfunction "1_1") (pintype "passive"))
      (node (ref "D2") (pin "2") (pinfunction "VDDA_2") (pintype "passive"))
      (node (ref "IND2") (pin "2") (pinfunction "2_2") (pintype "passive"))
    )
    (net (code "83") (name "Net-(D2-VDDD)") (class "Default")
      (node (ref "C12") (pin "1") (pinfunction "1_1") (pintype "passive"))
      (node (ref "C15") (pin "1") (pinfunction "1_1") (pintype "passive"))
      (node (ref "D2") (pin "4") (pinfunction "VDDD_4") (pintype "passive"))
      (node (ref "IND3") (pin "2") (pinfunction "2_2") (pintype "passive"))
    )
    (net (code "84") (name "Net-(D2-VDDSPK)") (class "Default")
      (node (ref "C13") (pin "1") (pinfunction "1_1") (pintype "passive"))
      (node (ref "C16") (pin "1") (pinfunction "1_1") (pintype "passive"))
      (node (ref "C18") (pin "1") (pinfunction "1_1") (pintype "passive"))
      (node (ref "C20") (pin "1") (pinfunction "1_1") (pintype "passive"))
      (node (ref "D2") (pin "17") (pinfunction "VDDSPK_17") (pintype "passive"))
      (node (ref "IND4") (pin "2") (pinfunction "2_2") (pintype "passive"))
    )
    (net (code "85") (name "Net-(D2-VREF)") (class "Default")
      (node (ref "C28") (pin "2") (pinfunction "2_2") (pintype "passive"))
      (node (ref "D2") (pin "18") (pinfunction "VREF_18") (pintype "passive"))
    )
    (net (code "86") (name "Net-(D3-A2)") (class "Default")
      (node (ref "D3") (pin "4") (pinfunction "A2_4") (pintype "bidirectional"))
      (node (ref "R78") (pin "1") (pinfunction "CCW_1") (pintype "passive"))
    )
    (net (code "87") (name "Net-(D3-B1)") (class "Default")
      (node (ref "D3") (pin "8") (pinfunction "B1_8") (pintype "bidirectional"))
      (node (ref "D7") (pin "1") (pinfunction "X1/CLK_1") (pintype "input"))
    )
    (net (code "88") (name "Net-(D7-OE)") (class "Default")
      (node (ref "D7") (pin "7") (pinfunction "OE_7") (pintype "passive"))
      (node (ref "R72") (pin "2") (pinfunction "CW_2") (pintype "passive"))
    )
    (net (code "89") (name "Net-(D7-S1)") (class "Default")
      (node (ref "D7") (pin "4") (pinfunction "S1_4") (pintype "power_in"))
      (node (ref "R71") (pin "2") (pinfunction "CW_2") (pintype "passive"))
    )
    (net (code "90") (name "Net-(D8-A0)") (class "Default")
      (node (ref "D8") (pin "1") (pinfunction "A0_1") (pintype "input"))
      (node (ref "R79") (pin "1") (pinfunction "CCW_1") (pintype "passive"))
    )
    (net (code "91") (name "Net-(D8-A1)") (class "Default")
      (node (ref "D8") (pin "2") (pinfunction "A1_2") (pintype "input"))
      (node (ref "R80") (pin "1") (pinfunction "CCW_1") (pintype "passive"))
    )
    (net (code "92") (name "Net-(D8-A2)") (class "Default")
      (node (ref "D8") (pin "3") (pinfunction "A2_3") (pintype "input"))
      (node (ref "R81") (pin "1") (pinfunction "CCW_1") (pintype "passive"))
    )
    (net (code "93") (name "Net-(D8-P3)") (class "Default")
      (node (ref "D8") (pin "7") (pinfunction "P3_7") (pintype "bidirectional"))
      (node (ref "R82") (pin "2") (pinfunction "CW_2") (pintype "passive"))
      (node (ref "VT11") (pin "1") (pinfunction "G_1") (pintype "passive"))
    )
    (net (code "94") (name "Net-(DA1-+IN)") (class "Default")
      (node (ref "C32") (pin "1") (pinfunction "1_1") (pintype "passive"))
      (node (ref "DA1") (pin "1") (pinfunction "+IN_1") (pintype "input"))
      (node (ref "IND7") (pin "2") (pinfunction "2_2") (pintype "passive"))
    )
    (net (code "95") (name "Net-(DA1--IN)") (class "Default")
      (node (ref "C37") (pin "1") (pinfunction "1_1") (pintype "passive"))
      (node (ref "DA1") (pin "2") (pinfunction "-IN_2") (pintype "input"))
      (node (ref "R37") (pin "2") (pinfunction "CW_2") (pintype "passive"))
    )
    (net (code "96") (name "Net-(DA1-OUT)") (class "Default")
      (node (ref "C36") (pin "1") (pinfunction "1_1") (pintype "passive"))
      (node (ref "C38") (pin "1") (pinfunction "1_1") (pintype "passive"))
      (node (ref "C39") (pin "1") (pinfunction "1_1") (pintype "passive"))
      (node (ref "DA1") (pin "4") (pinfunction "OUT_4") (pintype "output"))
      (node (ref "R41") (pin "1") (pinfunction "CCW_1") (pintype "passive"))
    )
    (net (code "97") (name "Net-(DA1-VCC)") (class "Default")
      (node (ref "C34") (pin "1") (pinfunction "1_1") (pintype "passive"))
      (node (ref "DA1") (pin "5") (pinfunction "VCC_5") (pintype "power_in"))
      (node (ref "IND8") (pin "2") (pinfunction "2_2") (pintype "passive"))
    )
    (net (code "98") (name "Net-(HL1-NEG)") (class "Default")
      (node (ref "HL1") (pin "2") (pinfunction "NEG_2") (pintype "passive"))
      (node (ref "R30") (pin "2") (pinfunction "CW_2") (pintype "passive"))
    )
    (net (code "99") (name "Net-(HL2-NEG)") (class "Default")
      (node (ref "HL2") (pin "2") (pinfunction "NEG_2") (pintype "passive"))
      (node (ref "R40") (pin "2") (pinfunction "CW_2") (pintype "passive"))
    )
    (net (code "100") (name "Net-(R1-CCW)") (class "Default")
      (node (ref "R1") (pin "1") (pinfunction "CCW_1") (pintype "passive"))
      (node (ref "R4") (pin "2") (pinfunction "CW_2") (pintype "passive"))
      (node (ref "R5") (pin "2") (pinfunction "CW_2") (pintype "passive"))
      (node (ref "R6") (pin "2") (pinfunction "CW_2") (pintype "passive"))
    )
    (net (code "101") (name "Net-(R2-CW)") (class "Default")
      (node (ref "R2") (pin "2") (pinfunction "CW_2") (pintype "passive"))
      (node (ref "X4") (pin "3") (pinfunction "3_3") (pintype "passive"))
    )
    (net (code "102") (name "Net-(R3-CCW)") (class "Default")
      (node (ref "C4") (pin "1") (pinfunction "1_1") (pintype "passive"))
      (node (ref "IND1") (pin "2") (pinfunction "2_2") (pintype "passive"))
      (node (ref "R3") (pin "1") (pinfunction "CCW_1") (pintype "passive"))
    )
    (net (code "103") (name "Net-(R3-CW)") (class "Default")
      (node (ref "R3") (pin "2") (pinfunction "CW_2") (pintype "passive"))
      (node (ref "X4") (pin "2") (pinfunction "2_2") (pintype "passive"))
    )
    (net (code "104") (name "Net-(R5-CCW)") (class "Default")
      (node (ref "R5") (pin "1") (pinfunction "CCW_1") (pintype "passive"))
      (node (ref "R8") (pin "2") (pinfunction "CW_2") (pintype "passive"))
      (node (ref "R9") (pin "2") (pinfunction "CW_2") (pintype "passive"))
      (node (ref "S1") (pin "1") (pinfunction "1_1") (pintype "passive"))
      (node (ref "VD6") (pin "4") (pinfunction "C_4") (pintype "passive"))
    )
    (net (code "105") (name "Net-(R10-CW)") (class "Default")
      (node (ref "R10") (pin "2") (pinfunction "CW_2") (pintype "passive"))
      (node (ref "R11") (pin "2") (pinfunction "CW_2") (pintype "passive"))
      (node (ref "R6") (pin "1") (pinfunction "CCW_1") (pintype "passive"))
      (node (ref "S2") (pin "1") (pinfunction "1_1") (pintype "passive"))
      (node (ref "VD6") (pin "3") (pinfunction "B_3") (pintype "passive"))
    )
    (net (code "106") (name "Net-(R12-CW)") (class "Default")
      (node (ref "R12") (pin "2") (pinfunction "CW_2") (pintype "passive"))
      (node (ref "R13") (pin "2") (pinfunction "CW_2") (pintype "passive"))
      (node (ref "R4") (pin "1") (pinfunction "CCW_1") (pintype "passive"))
      (node (ref "S3") (pin "1") (pinfunction "1_1") (pintype "passive"))
      (node (ref "VD6") (pin "2") (pinfunction "A_2") (pintype "passive"))
    )
    (net (code "107") (name "Net-(R14-CW)") (class "Default")
      (node (ref "C5") (pin "1") (pinfunction "1_1") (pintype "passive"))
      (node (ref "R14") (pin "2") (pinfunction "CW_2") (pintype "passive"))
      (node (ref "VD1") (pin "5") (pinfunction "C4_5") (pintype "passive"))
      (node (ref "X1") (pin "C2") (pinfunction "RST_C2") (pintype "input"))
    )
    (net (code "108") (name "Net-(R15-CW)") (class "Default")
      (node (ref "C7") (pin "1") (pinfunction "1_1") (pintype "passive"))
      (node (ref "R15") (pin "2") (pinfunction "CW_2") (pintype "passive"))
      (node (ref "VD1") (pin "1") (pinfunction "C1_1") (pintype "passive"))
      (node (ref "X1") (pin "C3") (pinfunction "CLK_C3") (pintype "input"))
    )
    (net (code "109") (name "Net-(R16-CW)") (class "Default")
      (node (ref "C9") (pin "1") (pinfunction "1_1") (pintype "passive"))
      (node (ref "R16") (pin "2") (pinfunction "CW_2") (pintype "passive"))
      (node (ref "VD1") (pin "3") (pinfunction "C2_3") (pintype "passive"))
      (node (ref "X1") (pin "C7") (pinfunction "I/O_C7") (pintype "bidirectional"))
    )
    (net (code "110") (name "Net-(R27-CW)") (class "Default")
      (node (ref "R27") (pin "2") (pinfunction "CW_2") (pintype "passive"))
      (node (ref "R28") (pin "2") (pinfunction "CW_2") (pintype "passive"))
      (node (ref "VT2") (pin "1") (pinfunction "B_1") (pintype "passive"))
    )
    (net (code "111") (name "Net-(R30-CCW)") (class "Default")
      (node (ref "R30") (pin "1") (pinfunction "CCW_1") (pintype "passive"))
      (node (ref "VT2") (pin "3") (pinfunction "C_3") (pintype "passive"))
    )
    (net (code "112") (name "Net-(R35-CW)") (class "Default")
      (node (ref "R35") (pin "2") (pinfunction "CW_2") (pintype "passive"))
      (node (ref "X6") (pin "2") (pinfunction "2_2") (pintype "passive"))
    )
    (net (code "113") (name "Net-(R36-CW)") (class "Default")
      (node (ref "R36") (pin "2") (pinfunction "CW_2") (pintype "passive"))
      (node (ref "R38") (pin "2") (pinfunction "CW_2") (pintype "passive"))
      (node (ref "VT3") (pin "1") (pinfunction "B_1") (pintype "passive"))
    )
    (net (code "114") (name "Net-(R37-CCW)") (class "Default")
      (node (ref "C36") (pin "2") (pinfunction "2_2") (pintype "passive"))
      (node (ref "R37") (pin "1") (pinfunction "CCW_1") (pintype "passive"))
    )
    (net (code "115") (name "Net-(R40-CCW)") (class "Default")
      (node (ref "R40") (pin "1") (pinfunction "CCW_1") (pintype "passive"))
      (node (ref "VT3") (pin "3") (pinfunction "C_3") (pintype "passive"))
    )
    (net (code "116") (name "Net-(R41-CW)") (class "Default")
      (node (ref "C37") (pin "2") (pinfunction "2_2") (pintype "passive"))
      (node (ref "R41") (pin "2") (pinfunction "CW_2") (pintype "passive"))
      (node (ref "R42") (pin "1") (pinfunction "CCW_1") (pintype "passive"))
    )
    (net (code "117") (name "Net-(R43-CCW)") (class "Default")
      (node (ref "C40") (pin "2") (pinfunction "2_2") (pintype "passive"))
      (node (ref "R43") (pin "1") (pinfunction "CCW_1") (pintype "passive"))
    )
    (net (code "118") (name "Net-(R45-CCW)") (class "Default")
      (node (ref "C44") (pin "2") (pinfunction "2_2") (pintype "passive"))
      (node (ref "L1") (pin "1") (pinfunction "1_1") (pintype "passive"))
      (node (ref "R45") (pin "1") (pinfunction "CCW_1") (pintype "passive"))
    )
    (net (code "119") (name "Net-(R73-CW)") (class "Default")
      (node (ref "R73") (pin "2") (pinfunction "CW_2") (pintype "passive"))
      (node (ref "R74") (pin "2") (pinfunction "CW_2") (pintype "passive"))
      (node (ref "VT10") (pin "1") (pinfunction "G_1") (pintype "passive"))
    )
    (net (code "120") (name "Net-(X10-SIG)") (class "Default")
      (node (ref "C41") (pin "1") (pinfunction "1_1") (pintype "passive"))
      (node (ref "L1") (pin "2") (pinfunction "2_2") (pintype "passive"))
      (node (ref "X10") (pin "1") (pinfunction "SIG_1") (pintype "bidirectional"))
    )
    (net (code "121") (name "Vamp") (class "Default")
      (node (ref "IND8") (pin "1") (pinfunction "1_1") (pintype "passive"))
    )
    (net (code "122") (name "unconnected-(D1-COEX1-Pad83)") (class "Default")
      (node (ref "D1") (pin "83") (pinfunction "COEX1_83") (pintype "bidirectional"))
    )
    (net (code "123") (name "unconnected-(D1-COEX2-Pad84)") (class "Default")
      (node (ref "D1") (pin "84") (pinfunction "COEX2_84") (pintype "bidirectional"))
    )
    (net (code "124") (name "unconnected-(D1-COEX3-Pad86)") (class "Default")
      (node (ref "D1") (pin "86") (pinfunction "COEX3_86") (pintype "bidirectional"))
    )
    (net (code "125") (name "unconnected-(D1-CTS-Pad67)") (class "Default")
      (node (ref "D1") (pin "67") (pinfunction "CTS_67") (pintype "input"))
    )
    (net (code "126") (name "unconnected-(D1-DCD-Pad70)") (class "Default")
      (node (ref "D1") (pin "70") (pinfunction "DCD_70") (pintype "output"))
    )
    (net (code "127") (name "unconnected-(D1-DTR-Pad72)") (class "Default")
      (node (ref "D1") (pin "72") (pinfunction "DTR_72") (pintype "input"))
    )
    (net (code "128") (name "unconnected-(D1-GPIO3-Pad33)") (class "Default")
      (node (ref "D1") (pin "33") (pinfunction "GPIO3_33") (pintype "bidirectional"))
    )
    (net (code "129") (name "unconnected-(D1-HSIC_DATA-Pad36)") (class "Default")
      (node (ref "D1") (pin "36") (pinfunction "HSIC_DATA_36") (pintype "bidirectional"))
    )
    (net (code "130") (name "unconnected-(D1-HSIC_STROBE-Pad35)") (class "Default")
      (node (ref "D1") (pin "35") (pinfunction "HSIC_STROBE_35") (pintype "output"))
    )
    (net (code "131") (name "unconnected-(D1-ISINK-Pad45)") (class "Default")
      (node (ref "D1") (pin "45") (pinfunction "ISINK_45") (pintype "input"))
    )
    (net (code "132") (name "unconnected-(D1-RI-Pad69)") (class "Default")
      (node (ref "D1") (pin "69") (pinfunction "RI_69") (pintype "output"))
    )
    (net (code "133") (name "unconnected-(D1-RTS-Pad66)") (class "Default")
      (node (ref "D1") (pin "66") (pinfunction "RTS_66") (pintype "output"))
    )
    (net (code "134") (name "unconnected-(D1-SDIO_CLK-Pad32)") (class "Default")
      (node (ref "D1") (pin "32") (pinfunction "SDIO_CLK_32") (pintype "output"))
    )
    (net (code "135") (name "unconnected-(D1-SDIO_CMD-Pad29)") (class "Default")
      (node (ref "D1") (pin "29") (pinfunction "SDIO_CMD_29") (pintype "output"))
    )
    (net (code "136") (name "unconnected-(D1-SDIO_DATA0-Pad30)") (class "Default")
      (node (ref "D1") (pin "30") (pinfunction "SDIO_DATA0_30") (pintype "bidirectional"))
    )
    (net (code "137") (name "unconnected-(D1-SDIO_DATA1-Pad27)") (class "Default")
      (node (ref "D1") (pin "27") (pinfunction "SDIO_DATA1_27") (pintype "bidirectional"))
    )
    (net (code "138") (name "unconnected-(D1-SDIO_DATA2-Pad28)") (class "Default")
      (node (ref "D1") (pin "28") (pinfunction "SDIO_DATA2_28") (pintype "bidirectional"))
    )
    (net (code "139") (name "unconnected-(D1-SDIO_DATA3-Pad31)") (class "Default")
      (node (ref "D1") (pin "31") (pinfunction "SDIO_DATA3_31") (pintype "bidirectional"))
    )
    (net (code "140") (name "unconnected-(D1-SPI_CLK-Pad6)") (class "Default")
      (node (ref "D1") (pin "6") (pinfunction "SPI_CLK_6") (pintype "output"))
    )
    (net (code "141") (name "unconnected-(D1-SPI_CS-Pad9)") (class "Default")
      (node (ref "D1") (pin "9") (pinfunction "SPI_CS_9") (pintype "output"))
    )
    (net (code "142") (name "unconnected-(D1-SPI_MISO-Pad7)") (class "Default")
      (node (ref "D1") (pin "7") (pinfunction "SPI_MISO_7") (pintype "input"))
    )
    (net (code "143") (name "unconnected-(D1-SPI_MOSI-Pad8)") (class "Default")
      (node (ref "D1") (pin "8") (pinfunction "SPI_MOSI_8") (pintype "output"))
    )
    (net (code "144") (name "unconnected-(D1-USB_ID-Pad16)") (class "Default")
      (node (ref "D1") (pin "16") (pinfunction "USB_ID_16") (pintype "input"))
    )
    (net (code "145") (name "unconnected-(D1-VDD_AUX-Pad44)") (class "Default")
      (node (ref "D1") (pin "44") (pinfunction "VDD_AUX_44") (pintype "power_in"))
    )
    (net (code "146") (name "unconnected-(D2-SPKOUT+-Pad14)") (class "Default")
      (node (ref "D2") (pin "14") (pinfunction "SPKOUT+_14") (pintype "passive"))
    )
    (net (code "147") (name "unconnected-(D2-SPKOUT--Pad16)") (class "Default")
      (node (ref "D2") (pin "16") (pinfunction "SPKOUT-_16") (pintype "passive"))
    )
    (net (code "148") (name "unconnected-(D7-X2-Pad8)") (class "Default")
      (node (ref "D7") (pin "8") (pinfunction "X2_8") (pintype "power_in"))
    )
    (net (code "149") (name "unconnected-(D8-~{INT}-Pad13)") (class "Default")
      (node (ref "D8") (pin "13") (pinfunction "~{INT}_13") (pintype "output"))
    )
    (net (code "150") (name "unconnected-(VD1-C3-Pad4)") (class "Default")
      (node (ref "VD1") (pin "4") (pinfunction "C3_4") (pintype "passive"))
    )
    (net (code "151") (name "unconnected-(VD5-A-Pad1)") (class "Default")
      (node (ref "VD5") (pin "1") (pinfunction "A_1") (pintype "passive"))
    )
    (net (code "152") (name "unconnected-(VD18-A-Pad1)") (class "Default")
      (node (ref "VD18") (pin "1") (pinfunction "A_1") (pintype "passive"))
    )
    (net (code "153") (name "unconnected-(X1-PadCD)") (class "Default")
      (node (ref "X1") (pin "CD") (pinfunction "CD_CD") (pintype "output"))
    )
    (net (code "154") (name "unconnected-(X1-PadCDL)") (class "Default")
      (node (ref "X1") (pin "CDL") (pinfunction "CDL_CDL") (pintype "output"))
    )
    (net (code "155") (name "unconnected-(X1-VPP-PadC6)") (class "Default")
      (node (ref "X1") (pin "C6") (pinfunction "VPP_C6") (pintype "passive"))
    )
    (net (code "156") (name "unconnected-(X2-CD-Pad9)") (class "Default")
      (node (ref "X2") (pin "9") (pinfunction "CD_9") (pintype "output"))
    )
    (net (code "157") (name "unconnected-(X3-ID-Pad4)") (class "Default")
      (node (ref "X3") (pin "4") (pinfunction "ID_4") (pintype "passive"))
    )
    (net (code "158") (name "unconnected-(X5-Pad1)") (class "Default")
      (node (ref "X5") (pin "1") (pinfunction "1_1") (pintype "passive"))
    )
    (net (code "159") (name "unconnected-(X5-Pad2)") (class "Default")
      (node (ref "X5") (pin "2") (pinfunction "2_2") (pintype "passive"))
    )
    (net (code "160") (name "unconnected-(X5-Pad3)") (class "Default")
      (node (ref "X5") (pin "3") (pinfunction "3_3") (pintype "passive"))
    )
    (net (code "161") (name "unconnected-(X7-Pad10)") (class "Default")
      (node (ref "X7") (pin "10") (pinfunction "10_10") (pintype "passive"))
    )
  )
)
